# SCH_Clock_2021-09-15.net
KiCad netlist of a schematic drawn in EasyEDA
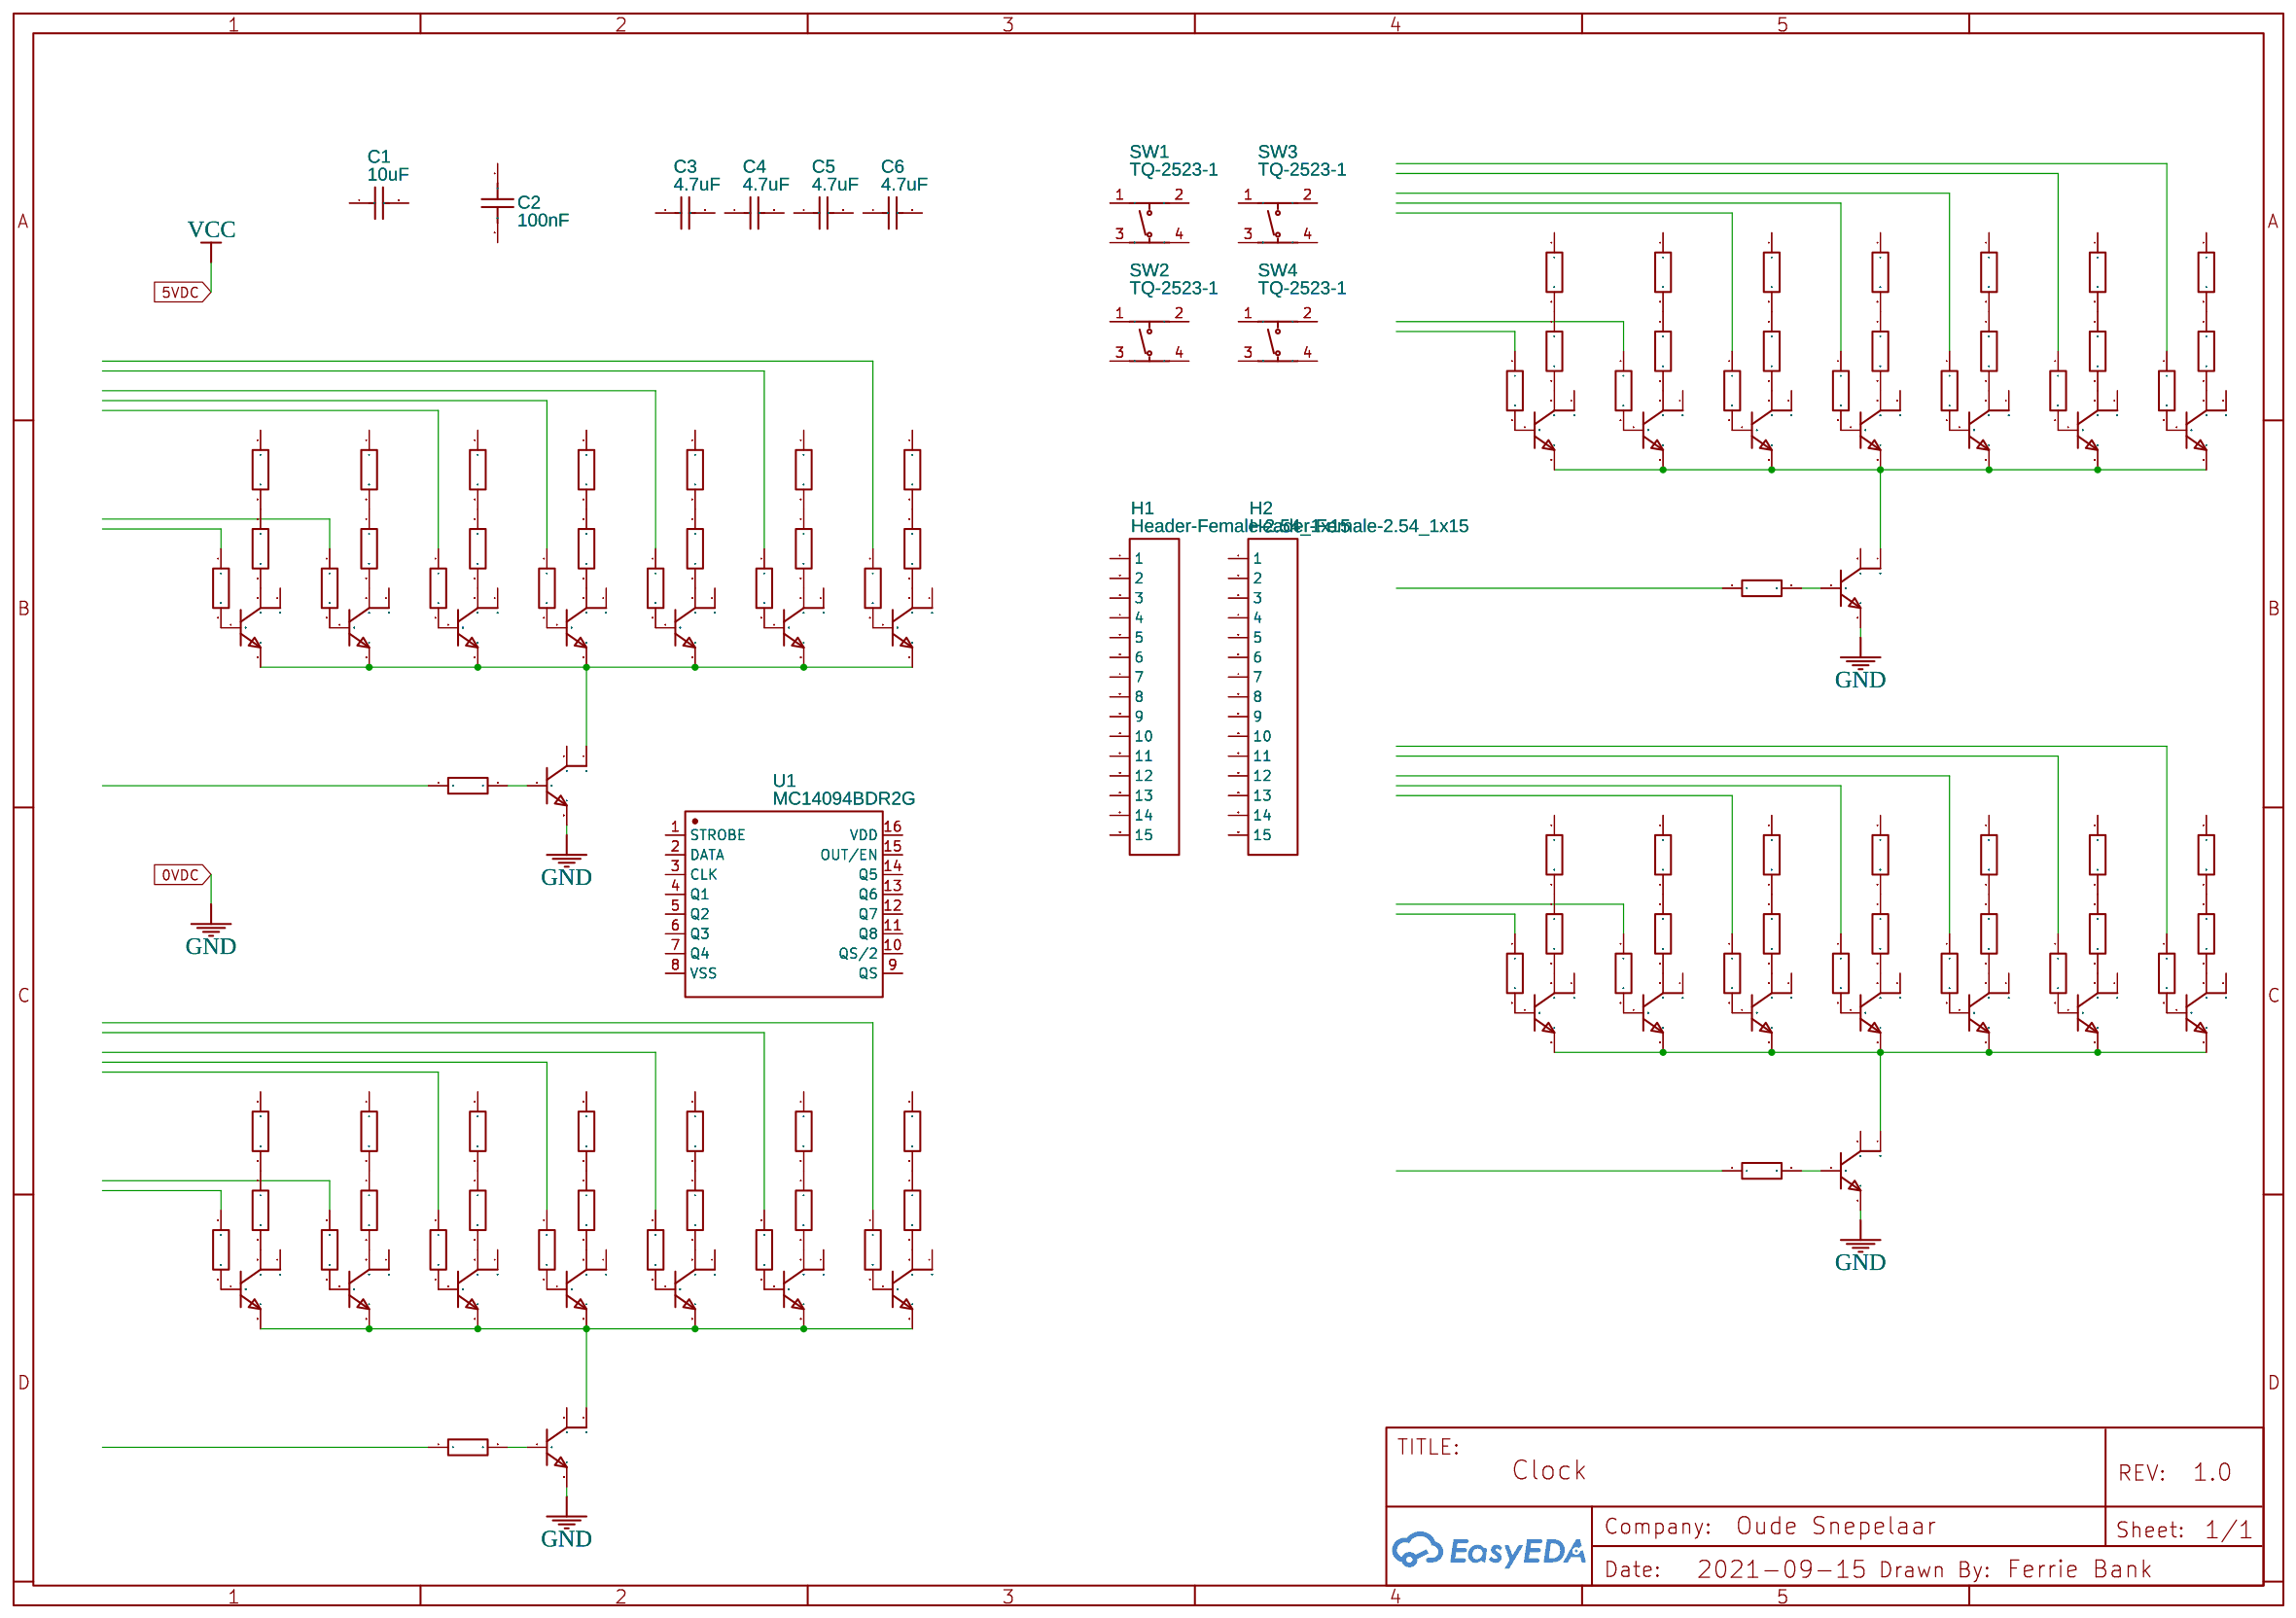
[diagram p0: schematic sheet]

(export (version "E")
  (design (tool "Eeschema 10.0.6"))
  (components
    (comp (ref "C1")
      (value "10uF")
      (fields
        (field (name "BOM_Manufacturer Part") "CL21A106KAYNNNE")
        (field (name "BOM_Supplier Part") "C15850")
      )
      (libsource (lib "") (part "CL21A106KAYNNNE"))
    )
    (comp (ref "C2")
      (value "100nF")
      (fields
        (field (name "BOM_Manufacturer Part") "CL10B104KB8WPNC")
        (field (name "BOM_Supplier Part") "C307348")
      )
      (libsource (lib "") (part "CL10B104KB8WPNC"))
    )
    (comp (ref "C3")
      (value "4.7uF")
      (fields
        (field (name "BOM_Manufacturer Part") "1206B475K500NT")
        (field (name "BOM_Supplier Part") "C29823")
      )
      (libsource (lib "") (part "1206B475K500NT"))
    )
    (comp (ref "C4")
      (value "4.7uF")
      (fields
        (field (name "BOM_Manufacturer Part") "1206B475K500NT")
        (field (name "BOM_Supplier Part") "C29823")
      )
      (libsource (lib "") (part "1206B475K500NT"))
    )
    (comp (ref "C5")
      (value "4.7uF")
      (fields
        (field (name "BOM_Manufacturer Part") "1206B475K500NT")
        (field (name "BOM_Supplier Part") "C29823")
      )
      (libsource (lib "") (part "1206B475K500NT"))
    )
    (comp (ref "C6")
      (value "4.7uF")
      (fields
        (field (name "BOM_Manufacturer Part") "1206B475K500NT")
        (field (name "BOM_Supplier Part") "C29823")
      )
      (libsource (lib "") (part "1206B475K500NT"))
    )
    (comp (ref "DGAQ1")
      (value "PZT2222A")
      (fields (field (name "BOM_Supplier Part") "C189428"))
      (libsource (lib "") (part "PZT2222A_1"))
    )
    (comp (ref "DGAQ2")
      (value "PZT2222A")
      (fields (field (name "BOM_Supplier Part") "C189428"))
      (libsource (lib "") (part "PZT2222A_1"))
    )
    (comp (ref "DGAQ3")
      (value "PZT2222A")
      (fields (field (name "BOM_Supplier Part") "C189428"))
      (libsource (lib "") (part "PZT2222A_1"))
    )
    (comp (ref "DGAQ4")
      (value "PZT2222A")
      (fields (field (name "BOM_Supplier Part") "C189428"))
      (libsource (lib "") (part "PZT2222A_1"))
    )
    (comp (ref "DGAQ5")
      (value "PZT2222A")
      (fields (field (name "BOM_Supplier Part") "C189428"))
      (libsource (lib "") (part "PZT2222A_1"))
    )
    (comp (ref "DGAQ6")
      (value "PZT2222A")
      (fields (field (name "BOM_Supplier Part") "C189428"))
      (libsource (lib "") (part "PZT2222A_1"))
    )
    (comp (ref "DGAQ7")
      (value "PZT2222A")
      (fields (field (name "BOM_Supplier Part") "C189428"))
      (libsource (lib "") (part "PZT2222A_1"))
    )
    (comp (ref "DGAQ8")
      (value "PZT2222A")
      (fields (field (name "BOM_Supplier Part") "C189428"))
      (libsource (lib "") (part "PZT2222A_1"))
    )
    (comp (ref "DGAR1")
      (value "75")
      (fields
        (field (name "BOM_Manufacturer Part") "0603WAF750JT5E")
        (field (name "BOM_Supplier Part") "C4275")
      )
      (libsource (lib "") (part "0603WAF750JT5E_2"))
    )
    (comp (ref "DGAR2")
      (value "75")
      (fields
        (field (name "BOM_Manufacturer Part") "0603WAF750JT5E")
        (field (name "BOM_Supplier Part") "C4275")
      )
      (libsource (lib "") (part "0603WAF750JT5E_2"))
    )
    (comp (ref "DGAR3")
      (value "75")
      (fields
        (field (name "BOM_Manufacturer Part") "0603WAF750JT5E")
        (field (name "BOM_Supplier Part") "C4275")
      )
      (libsource (lib "") (part "0603WAF750JT5E_2"))
    )
    (comp (ref "DGAR4")
      (value "75")
      (fields
        (field (name "BOM_Manufacturer Part") "0603WAF750JT5E")
        (field (name "BOM_Supplier Part") "C4275")
      )
      (libsource (lib "") (part "0603WAF750JT5E_2"))
    )
    (comp (ref "DGAR5")
      (value "75")
      (fields
        (field (name "BOM_Manufacturer Part") "0603WAF750JT5E")
        (field (name "BOM_Supplier Part") "C4275")
      )
      (libsource (lib "") (part "0603WAF750JT5E_2"))
    )
    (comp (ref "DGAR6")
      (value "75")
      (fields
        (field (name "BOM_Manufacturer Part") "0603WAF750JT5E")
        (field (name "BOM_Supplier Part") "C4275")
      )
      (libsource (lib "") (part "0603WAF750JT5E_2"))
    )
    (comp (ref "DGAR7")
      (value "75")
      (fields
        (field (name "BOM_Manufacturer Part") "0603WAF750JT5E")
        (field (name "BOM_Supplier Part") "C4275")
      )
      (libsource (lib "") (part "0603WAF750JT5E_2"))
    )
    (comp (ref "DGAR8")
      (value "75")
      (fields
        (field (name "BOM_Manufacturer Part") "0603WAF750JT5E")
        (field (name "BOM_Supplier Part") "C4275")
      )
      (libsource (lib "") (part "0603WAF750JT5E_2"))
    )
    (comp (ref "DGAR9")
      (value "75")
      (fields
        (field (name "BOM_Manufacturer Part") "0603WAF750JT5E")
        (field (name "BOM_Supplier Part") "C4275")
      )
      (libsource (lib "") (part "0603WAF750JT5E_2"))
    )
    (comp (ref "DGAR10")
      (value "75")
      (fields
        (field (name "BOM_Manufacturer Part") "0603WAF750JT5E")
        (field (name "BOM_Supplier Part") "C4275")
      )
      (libsource (lib "") (part "0603WAF750JT5E_2"))
    )
    (comp (ref "DGAR11")
      (value "75")
      (fields
        (field (name "BOM_Manufacturer Part") "0603WAF750JT5E")
        (field (name "BOM_Supplier Part") "C4275")
      )
      (libsource (lib "") (part "0603WAF750JT5E_2"))
    )
    (comp (ref "DGAR12")
      (value "75")
      (fields
        (field (name "BOM_Manufacturer Part") "0603WAF750JT5E")
        (field (name "BOM_Supplier Part") "C4275")
      )
      (libsource (lib "") (part "0603WAF750JT5E_2"))
    )
    (comp (ref "DGAR13")
      (value "75")
      (fields
        (field (name "BOM_Manufacturer Part") "0603WAF750JT5E")
        (field (name "BOM_Supplier Part") "C4275")
      )
      (libsource (lib "") (part "0603WAF750JT5E_2"))
    )
    (comp (ref "DGAR14")
      (value "75")
      (fields
        (field (name "BOM_Manufacturer Part") "0603WAF750JT5E")
        (field (name "BOM_Supplier Part") "C4275")
      )
      (libsource (lib "") (part "0603WAF750JT5E_2"))
    )
    (comp (ref "DGAR15")
      (value "33")
      (fields
        (field (name "BOM_Manufacturer Part") "0603WAF330JT5E")
        (field (name "BOM_Supplier Part") "C23140")
      )
      (libsource (lib "") (part "0603WAF330JT5E_6"))
    )
    (comp (ref "DGAR16")
      (value "33")
      (fields
        (field (name "BOM_Manufacturer Part") "0603WAF330JT5E")
        (field (name "BOM_Supplier Part") "C23140")
      )
      (libsource (lib "") (part "0603WAF330JT5E_1"))
    )
    (comp (ref "DGAR17")
      (value "33")
      (fields
        (field (name "BOM_Manufacturer Part") "0603WAF330JT5E")
        (field (name "BOM_Supplier Part") "C23140")
      )
      (libsource (lib "") (part "0603WAF330JT5E_1"))
    )
    (comp (ref "DGAR18")
      (value "33")
      (fields
        (field (name "BOM_Manufacturer Part") "0603WAF330JT5E")
        (field (name "BOM_Supplier Part") "C23140")
      )
      (libsource (lib "") (part "0603WAF330JT5E_1"))
    )
    (comp (ref "DGAR19")
      (value "33")
      (fields
        (field (name "BOM_Manufacturer Part") "0603WAF330JT5E")
        (field (name "BOM_Supplier Part") "C23140")
      )
      (libsource (lib "") (part "0603WAF330JT5E_1"))
    )
    (comp (ref "DGAR20")
      (value "33")
      (fields
        (field (name "BOM_Manufacturer Part") "0603WAF330JT5E")
        (field (name "BOM_Supplier Part") "C23140")
      )
      (libsource (lib "") (part "0603WAF330JT5E_1"))
    )
    (comp (ref "DGAR21")
      (value "33")
      (fields
        (field (name "BOM_Manufacturer Part") "0603WAF330JT5E")
        (field (name "BOM_Supplier Part") "C23140")
      )
      (libsource (lib "") (part "0603WAF330JT5E_1"))
    )
    (comp (ref "DGAR22")
      (value "33")
      (fields
        (field (name "BOM_Manufacturer Part") "0603WAF330JT5E")
        (field (name "BOM_Supplier Part") "C23140")
      )
      (libsource (lib "") (part "0603WAF330JT5E_1"))
    )
    (comp (ref "DGBQ1")
      (value "PZT2222A")
      (fields (field (name "BOM_Supplier Part") "C189428"))
      (libsource (lib "") (part "PZT2222A"))
    )
    (comp (ref "DGBQ2")
      (value "PZT2222A")
      (fields (field (name "BOM_Supplier Part") "C189428"))
      (libsource (lib "") (part "PZT2222A"))
    )
    (comp (ref "DGBQ3")
      (value "PZT2222A")
      (fields (field (name "BOM_Supplier Part") "C189428"))
      (libsource (lib "") (part "PZT2222A"))
    )
    (comp (ref "DGBQ4")
      (value "PZT2222A")
      (fields (field (name "BOM_Supplier Part") "C189428"))
      (libsource (lib "") (part "PZT2222A"))
    )
    (comp (ref "DGBQ5")
      (value "PZT2222A")
      (fields (field (name "BOM_Supplier Part") "C189428"))
      (libsource (lib "") (part "PZT2222A"))
    )
    (comp (ref "DGBQ6")
      (value "PZT2222A")
      (fields (field (name "BOM_Supplier Part") "C189428"))
      (libsource (lib "") (part "PZT2222A"))
    )
    (comp (ref "DGBQ7")
      (value "PZT2222A")
      (fields (field (name "BOM_Supplier Part") "C189428"))
      (libsource (lib "") (part "PZT2222A"))
    )
    (comp (ref "DGBQ8")
      (value "PZT2222A")
      (fields (field (name "BOM_Supplier Part") "C189428"))
      (libsource (lib "") (part "PZT2222A"))
    )
    (comp (ref "DGBR1")
      (value "75")
      (fields
        (field (name "BOM_Manufacturer Part") "0603WAF750JT5E")
        (field (name "BOM_Supplier Part") "C4275")
      )
      (libsource (lib "") (part "0603WAF750JT5E_3"))
    )
    (comp (ref "DGBR2")
      (value "75")
      (fields
        (field (name "BOM_Manufacturer Part") "0603WAF750JT5E")
        (field (name "BOM_Supplier Part") "C4275")
      )
      (libsource (lib "") (part "0603WAF750JT5E_3"))
    )
    (comp (ref "DGBR3")
      (value "75")
      (fields
        (field (name "BOM_Manufacturer Part") "0603WAF750JT5E")
        (field (name "BOM_Supplier Part") "C4275")
      )
      (libsource (lib "") (part "0603WAF750JT5E_3"))
    )
    (comp (ref "DGBR4")
      (value "75")
      (fields
        (field (name "BOM_Manufacturer Part") "0603WAF750JT5E")
        (field (name "BOM_Supplier Part") "C4275")
      )
      (libsource (lib "") (part "0603WAF750JT5E_3"))
    )
    (comp (ref "DGBR5")
      (value "75")
      (fields
        (field (name "BOM_Manufacturer Part") "0603WAF750JT5E")
        (field (name "BOM_Supplier Part") "C4275")
      )
      (libsource (lib "") (part "0603WAF750JT5E_3"))
    )
    (comp (ref "DGBR6")
      (value "75")
      (fields
        (field (name "BOM_Manufacturer Part") "0603WAF750JT5E")
        (field (name "BOM_Supplier Part") "C4275")
      )
      (libsource (lib "") (part "0603WAF750JT5E_3"))
    )
    (comp (ref "DGBR7")
      (value "75")
      (fields
        (field (name "BOM_Manufacturer Part") "0603WAF750JT5E")
        (field (name "BOM_Supplier Part") "C4275")
      )
      (libsource (lib "") (part "0603WAF750JT5E_3"))
    )
    (comp (ref "DGBR8")
      (value "75")
      (fields
        (field (name "BOM_Manufacturer Part") "0603WAF750JT5E")
        (field (name "BOM_Supplier Part") "C4275")
      )
      (libsource (lib "") (part "0603WAF750JT5E_3"))
    )
    (comp (ref "DGBR9")
      (value "75")
      (fields
        (field (name "BOM_Manufacturer Part") "0603WAF750JT5E")
        (field (name "BOM_Supplier Part") "C4275")
      )
      (libsource (lib "") (part "0603WAF750JT5E_3"))
    )
    (comp (ref "DGBR10")
      (value "75")
      (fields
        (field (name "BOM_Manufacturer Part") "0603WAF750JT5E")
        (field (name "BOM_Supplier Part") "C4275")
      )
      (libsource (lib "") (part "0603WAF750JT5E_3"))
    )
    (comp (ref "DGBR11")
      (value "75")
      (fields
        (field (name "BOM_Manufacturer Part") "0603WAF750JT5E")
        (field (name "BOM_Supplier Part") "C4275")
      )
      (libsource (lib "") (part "0603WAF750JT5E_3"))
    )
    (comp (ref "DGBR12")
      (value "75")
      (fields
        (field (name "BOM_Manufacturer Part") "0603WAF750JT5E")
        (field (name "BOM_Supplier Part") "C4275")
      )
      (libsource (lib "") (part "0603WAF750JT5E_3"))
    )
    (comp (ref "DGBR13")
      (value "75")
      (fields
        (field (name "BOM_Manufacturer Part") "0603WAF750JT5E")
        (field (name "BOM_Supplier Part") "C4275")
      )
      (libsource (lib "") (part "0603WAF750JT5E_3"))
    )
    (comp (ref "DGBR14")
      (value "75")
      (fields
        (field (name "BOM_Manufacturer Part") "0603WAF750JT5E")
        (field (name "BOM_Supplier Part") "C4275")
      )
      (libsource (lib "") (part "0603WAF750JT5E_3"))
    )
    (comp (ref "DGBR15")
      (value "33")
      (fields
        (field (name "BOM_Manufacturer Part") "0603WAF330JT5E")
        (field (name "BOM_Supplier Part") "C23140")
      )
      (libsource (lib "") (part "0603WAF330JT5E_5"))
    )
    (comp (ref "DGBR16")
      (value "33")
      (fields
        (field (name "BOM_Manufacturer Part") "0603WAF330JT5E")
        (field (name "BOM_Supplier Part") "C23140")
      )
      (libsource (lib "") (part "0603WAF330JT5E_3"))
    )
    (comp (ref "DGBR17")
      (value "33")
      (fields
        (field (name "BOM_Manufacturer Part") "0603WAF330JT5E")
        (field (name "BOM_Supplier Part") "C23140")
      )
      (libsource (lib "") (part "0603WAF330JT5E_3"))
    )
    (comp (ref "DGBR18")
      (value "33")
      (fields
        (field (name "BOM_Manufacturer Part") "0603WAF330JT5E")
        (field (name "BOM_Supplier Part") "C23140")
      )
      (libsource (lib "") (part "0603WAF330JT5E_3"))
    )
    (comp (ref "DGBR19")
      (value "33")
      (fields
        (field (name "BOM_Manufacturer Part") "0603WAF330JT5E")
        (field (name "BOM_Supplier Part") "C23140")
      )
      (libsource (lib "") (part "0603WAF330JT5E_3"))
    )
    (comp (ref "DGBR20")
      (value "33")
      (fields
        (field (name "BOM_Manufacturer Part") "0603WAF330JT5E")
        (field (name "BOM_Supplier Part") "C23140")
      )
      (libsource (lib "") (part "0603WAF330JT5E_3"))
    )
    (comp (ref "DGBR21")
      (value "33")
      (fields
        (field (name "BOM_Manufacturer Part") "0603WAF330JT5E")
        (field (name "BOM_Supplier Part") "C23140")
      )
      (libsource (lib "") (part "0603WAF330JT5E_3"))
    )
    (comp (ref "DGBR22")
      (value "33")
      (fields
        (field (name "BOM_Manufacturer Part") "0603WAF330JT5E")
        (field (name "BOM_Supplier Part") "C23140")
      )
      (libsource (lib "") (part "0603WAF330JT5E_3"))
    )
    (comp (ref "DGCQ1")
      (value "PZT2222A")
      (fields (field (name "BOM_Supplier Part") "C189428"))
      (libsource (lib "") (part "PZT2222A_3"))
    )
    (comp (ref "DGCQ2")
      (value "PZT2222A")
      (fields (field (name "BOM_Supplier Part") "C189428"))
      (libsource (lib "") (part "PZT2222A_3"))
    )
    (comp (ref "DGCQ3")
      (value "PZT2222A")
      (fields (field (name "BOM_Supplier Part") "C189428"))
      (libsource (lib "") (part "PZT2222A_3"))
    )
    (comp (ref "DGCQ4")
      (value "PZT2222A")
      (fields (field (name "BOM_Supplier Part") "C189428"))
      (libsource (lib "") (part "PZT2222A_3"))
    )
    (comp (ref "DGCQ5")
      (value "PZT2222A")
      (fields (field (name "BOM_Supplier Part") "C189428"))
      (libsource (lib "") (part "PZT2222A_3"))
    )
    (comp (ref "DGCQ6")
      (value "PZT2222A")
      (fields (field (name "BOM_Supplier Part") "C189428"))
      (libsource (lib "") (part "PZT2222A_3"))
    )
    (comp (ref "DGCQ7")
      (value "PZT2222A")
      (fields (field (name "BOM_Supplier Part") "C189428"))
      (libsource (lib "") (part "PZT2222A_3"))
    )
    (comp (ref "DGCQ8")
      (value "PZT2222A")
      (fields (field (name "BOM_Supplier Part") "C189428"))
      (libsource (lib "") (part "PZT2222A_3"))
    )
    (comp (ref "DGCR1")
      (value "75")
      (fields
        (field (name "BOM_Manufacturer Part") "0603WAF750JT5E")
        (field (name "BOM_Supplier Part") "C4275")
      )
      (libsource (lib "") (part "0603WAF750JT5E"))
    )
    (comp (ref "DGCR2")
      (value "75")
      (fields
        (field (name "BOM_Manufacturer Part") "0603WAF750JT5E")
        (field (name "BOM_Supplier Part") "C4275")
      )
      (libsource (lib "") (part "0603WAF750JT5E"))
    )
    (comp (ref "DGCR3")
      (value "75")
      (fields
        (field (name "BOM_Manufacturer Part") "0603WAF750JT5E")
        (field (name "BOM_Supplier Part") "C4275")
      )
      (libsource (lib "") (part "0603WAF750JT5E"))
    )
    (comp (ref "DGCR4")
      (value "75")
      (fields
        (field (name "BOM_Manufacturer Part") "0603WAF750JT5E")
        (field (name "BOM_Supplier Part") "C4275")
      )
      (libsource (lib "") (part "0603WAF750JT5E"))
    )
    (comp (ref "DGCR5")
      (value "75")
      (fields
        (field (name "BOM_Manufacturer Part") "0603WAF750JT5E")
        (field (name "BOM_Supplier Part") "C4275")
      )
      (libsource (lib "") (part "0603WAF750JT5E"))
    )
    (comp (ref "DGCR6")
      (value "75")
      (fields
        (field (name "BOM_Manufacturer Part") "0603WAF750JT5E")
        (field (name "BOM_Supplier Part") "C4275")
      )
      (libsource (lib "") (part "0603WAF750JT5E"))
    )
    (comp (ref "DGCR7")
      (value "75")
      (fields
        (field (name "BOM_Manufacturer Part") "0603WAF750JT5E")
        (field (name "BOM_Supplier Part") "C4275")
      )
      (libsource (lib "") (part "0603WAF750JT5E"))
    )
    (comp (ref "DGCR8")
      (value "75")
      (fields
        (field (name "BOM_Manufacturer Part") "0603WAF750JT5E")
        (field (name "BOM_Supplier Part") "C4275")
      )
      (libsource (lib "") (part "0603WAF750JT5E"))
    )
    (comp (ref "DGCR9")
      (value "75")
      (fields
        (field (name "BOM_Manufacturer Part") "0603WAF750JT5E")
        (field (name "BOM_Supplier Part") "C4275")
      )
      (libsource (lib "") (part "0603WAF750JT5E"))
    )
    (comp (ref "DGCR10")
      (value "75")
      (fields
        (field (name "BOM_Manufacturer Part") "0603WAF750JT5E")
        (field (name "BOM_Supplier Part") "C4275")
      )
      (libsource (lib "") (part "0603WAF750JT5E"))
    )
    (comp (ref "DGCR11")
      (value "75")
      (fields
        (field (name "BOM_Manufacturer Part") "0603WAF750JT5E")
        (field (name "BOM_Supplier Part") "C4275")
      )
      (libsource (lib "") (part "0603WAF750JT5E"))
    )
    (comp (ref "DGCR12")
      (value "75")
      (fields
        (field (name "BOM_Manufacturer Part") "0603WAF750JT5E")
        (field (name "BOM_Supplier Part") "C4275")
      )
      (libsource (lib "") (part "0603WAF750JT5E"))
    )
    (comp (ref "DGCR13")
      (value "75")
      (fields
        (field (name "BOM_Manufacturer Part") "0603WAF750JT5E")
        (field (name "BOM_Supplier Part") "C4275")
      )
      (libsource (lib "") (part "0603WAF750JT5E"))
    )
    (comp (ref "DGCR14")
      (value "75")
      (fields
        (field (name "BOM_Manufacturer Part") "0603WAF750JT5E")
        (field (name "BOM_Supplier Part") "C4275")
      )
      (libsource (lib "") (part "0603WAF750JT5E"))
    )
    (comp (ref "DGCR15")
      (value "33")
      (fields
        (field (name "BOM_Manufacturer Part") "0603WAF330JT5E")
        (field (name "BOM_Supplier Part") "C23140")
      )
      (libsource (lib "") (part "0603WAF330JT5E_4"))
    )
    (comp (ref "DGCR16")
      (value "33")
      (fields
        (field (name "BOM_Manufacturer Part") "0603WAF330JT5E")
        (field (name "BOM_Supplier Part") "C23140")
      )
      (libsource (lib "") (part "0603WAF330JT5E_2"))
    )
    (comp (ref "DGCR17")
      (value "33")
      (fields
        (field (name "BOM_Manufacturer Part") "0603WAF330JT5E")
        (field (name "BOM_Supplier Part") "C23140")
      )
      (libsource (lib "") (part "0603WAF330JT5E_2"))
    )
    (comp (ref "DGCR18")
      (value "33")
      (fields
        (field (name "BOM_Manufacturer Part") "0603WAF330JT5E")
        (field (name "BOM_Supplier Part") "C23140")
      )
      (libsource (lib "") (part "0603WAF330JT5E_2"))
    )
    (comp (ref "DGCR19")
      (value "33")
      (fields
        (field (name "BOM_Manufacturer Part") "0603WAF330JT5E")
        (field (name "BOM_Supplier Part") "C23140")
      )
      (libsource (lib "") (part "0603WAF330JT5E_2"))
    )
    (comp (ref "DGCR20")
      (value "33")
      (fields
        (field (name "BOM_Manufacturer Part") "0603WAF330JT5E")
        (field (name "BOM_Supplier Part") "C23140")
      )
      (libsource (lib "") (part "0603WAF330JT5E_2"))
    )
    (comp (ref "DGCR21")
      (value "33")
      (fields
        (field (name "BOM_Manufacturer Part") "0603WAF330JT5E")
        (field (name "BOM_Supplier Part") "C23140")
      )
      (libsource (lib "") (part "0603WAF330JT5E_2"))
    )
    (comp (ref "DGCR22")
      (value "33")
      (fields
        (field (name "BOM_Manufacturer Part") "0603WAF330JT5E")
        (field (name "BOM_Supplier Part") "C23140")
      )
      (libsource (lib "") (part "0603WAF330JT5E_2"))
    )
    (comp (ref "DGDQ1")
      (value "PZT2222A")
      (fields (field (name "BOM_Supplier Part") "C189428"))
      (libsource (lib "") (part "PZT2222A_2"))
    )
    (comp (ref "DGDQ2")
      (value "PZT2222A")
      (fields (field (name "BOM_Supplier Part") "C189428"))
      (libsource (lib "") (part "PZT2222A_2"))
    )
    (comp (ref "DGDQ3")
      (value "PZT2222A")
      (fields (field (name "BOM_Supplier Part") "C189428"))
      (libsource (lib "") (part "PZT2222A_2"))
    )
    (comp (ref "DGDQ4")
      (value "PZT2222A")
      (fields (field (name "BOM_Supplier Part") "C189428"))
      (libsource (lib "") (part "PZT2222A_2"))
    )
    (comp (ref "DGDQ5")
      (value "PZT2222A")
      (fields (field (name "BOM_Supplier Part") "C189428"))
      (libsource (lib "") (part "PZT2222A_2"))
    )
    (comp (ref "DGDQ6")
      (value "PZT2222A")
      (fields (field (name "BOM_Supplier Part") "C189428"))
      (libsource (lib "") (part "PZT2222A_2"))
    )
    (comp (ref "DGDQ7")
      (value "PZT2222A")
      (fields (field (name "BOM_Supplier Part") "C189428"))
      (libsource (lib "") (part "PZT2222A_2"))
    )
    (comp (ref "DGDQ8")
      (value "PZT2222A")
      (fields (field (name "BOM_Supplier Part") "C189428"))
      (libsource (lib "") (part "PZT2222A_2"))
    )
    (comp (ref "DGDR1")
      (value "75")
      (fields
        (field (name "BOM_Manufacturer Part") "0603WAF750JT5E")
        (field (name "BOM_Supplier Part") "C4275")
      )
      (libsource (lib "") (part "0603WAF750JT5E_1"))
    )
    (comp (ref "DGDR2")
      (value "75")
      (fields
        (field (name "BOM_Manufacturer Part") "0603WAF750JT5E")
        (field (name "BOM_Supplier Part") "C4275")
      )
      (libsource (lib "") (part "0603WAF750JT5E_1"))
    )
    (comp (ref "DGDR3")
      (value "75")
      (fields
        (field (name "BOM_Manufacturer Part") "0603WAF750JT5E")
        (field (name "BOM_Supplier Part") "C4275")
      )
      (libsource (lib "") (part "0603WAF750JT5E_1"))
    )
    (comp (ref "DGDR4")
      (value "75")
      (fields
        (field (name "BOM_Manufacturer Part") "0603WAF750JT5E")
        (field (name "BOM_Supplier Part") "C4275")
      )
      (libsource (lib "") (part "0603WAF750JT5E_1"))
    )
    (comp (ref "DGDR5")
      (value "75")
      (fields
        (field (name "BOM_Manufacturer Part") "0603WAF750JT5E")
        (field (name "BOM_Supplier Part") "C4275")
      )
      (libsource (lib "") (part "0603WAF750JT5E_1"))
    )
    (comp (ref "DGDR6")
      (value "75")
      (fields
        (field (name "BOM_Manufacturer Part") "0603WAF750JT5E")
        (field (name "BOM_Supplier Part") "C4275")
      )
      (libsource (lib "") (part "0603WAF750JT5E_1"))
    )
    (comp (ref "DGDR7")
      (value "75")
      (fields
        (field (name "BOM_Manufacturer Part") "0603WAF750JT5E")
        (field (name "BOM_Supplier Part") "C4275")
      )
      (libsource (lib "") (part "0603WAF750JT5E_1"))
    )
    (comp (ref "DGDR8")
      (value "75")
      (fields
        (field (name "BOM_Manufacturer Part") "0603WAF750JT5E")
        (field (name "BOM_Supplier Part") "C4275")
      )
      (libsource (lib "") (part "0603WAF750JT5E_1"))
    )
    (comp (ref "DGDR9")
      (value "75")
      (fields
        (field (name "BOM_Manufacturer Part") "0603WAF750JT5E")
        (field (name "BOM_Supplier Part") "C4275")
      )
      (libsource (lib "") (part "0603WAF750JT5E_1"))
    )
    (comp (ref "DGDR10")
      (value "75")
      (fields
        (field (name "BOM_Manufacturer Part") "0603WAF750JT5E")
        (field (name "BOM_Supplier Part") "C4275")
      )
      (libsource (lib "") (part "0603WAF750JT5E_1"))
    )
    (comp (ref "DGDR11")
      (value "75")
      (fields
        (field (name "BOM_Manufacturer Part") "0603WAF750JT5E")
        (field (name "BOM_Supplier Part") "C4275")
      )
      (libsource (lib "") (part "0603WAF750JT5E_1"))
    )
    (comp (ref "DGDR12")
      (value "75")
      (fields
        (field (name "BOM_Manufacturer Part") "0603WAF750JT5E")
        (field (name "BOM_Supplier Part") "C4275")
      )
      (libsource (lib "") (part "0603WAF750JT5E_1"))
    )
    (comp (ref "DGDR13")
      (value "75")
      (fields
        (field (name "BOM_Manufacturer Part") "0603WAF750JT5E")
        (field (name "BOM_Supplier Part") "C4275")
      )
      (libsource (lib "") (part "0603WAF750JT5E_1"))
    )
    (comp (ref "DGDR14")
      (value "75")
      (fields
        (field (name "BOM_Manufacturer Part") "0603WAF750JT5E")
        (field (name "BOM_Supplier Part") "C4275")
      )
      (libsource (lib "") (part "0603WAF750JT5E_1"))
    )
    (comp (ref "DGDR15")
      (value "33")
      (fields
        (field (name "BOM_Manufacturer Part") "0603WAF330JT5E")
        (field (name "BOM_Supplier Part") "C23140")
      )
      (libsource (lib "") (part "0603WAF330JT5E_7"))
    )
    (comp (ref "DGDR16")
      (value "33")
      (fields
        (field (name "BOM_Manufacturer Part") "0603WAF330JT5E")
        (field (name "BOM_Supplier Part") "C23140")
      )
      (libsource (lib "") (part "0603WAF330JT5E"))
    )
    (comp (ref "DGDR17")
      (value "33")
      (fields
        (field (name "BOM_Manufacturer Part") "0603WAF330JT5E")
        (field (name "BOM_Supplier Part") "C23140")
      )
      (libsource (lib "") (part "0603WAF330JT5E"))
    )
    (comp (ref "DGDR18")
      (value "33")
      (fields
        (field (name "BOM_Manufacturer Part") "0603WAF330JT5E")
        (field (name "BOM_Supplier Part") "C23140")
      )
      (libsource (lib "") (part "0603WAF330JT5E"))
    )
    (comp (ref "DGDR19")
      (value "33")
      (fields
        (field (name "BOM_Manufacturer Part") "0603WAF330JT5E")
        (field (name "BOM_Supplier Part") "C23140")
      )
      (libsource (lib "") (part "0603WAF330JT5E"))
    )
    (comp (ref "DGDR20")
      (value "33")
      (fields
        (field (name "BOM_Manufacturer Part") "0603WAF330JT5E")
        (field (name "BOM_Supplier Part") "C23140")
      )
      (libsource (lib "") (part "0603WAF330JT5E"))
    )
    (comp (ref "DGDR21")
      (value "33")
      (fields
        (field (name "BOM_Manufacturer Part") "0603WAF330JT5E")
        (field (name "BOM_Supplier Part") "C23140")
      )
      (libsource (lib "") (part "0603WAF330JT5E"))
    )
    (comp (ref "DGDR22")
      (value "33")
      (fields
        (field (name "BOM_Manufacturer Part") "0603WAF330JT5E")
        (field (name "BOM_Supplier Part") "C23140")
      )
      (libsource (lib "") (part "0603WAF330JT5E"))
    )
    (comp (ref "H1")
      (value "Header-Female-2.54_1x15")
      (fields
        (field (name "BOM_Manufacturer Part") "220S-1*15P H=8.5MM Ytype Gold-plated")
        (field (name "BOM_Supplier Part") "C124408")
      )
      (libsource (lib "") (part "Header-Female-2.54_1x15"))
    )
    (comp (ref "H2")
      (value "Header-Female-2.54_1x15")
      (fields
        (field (name "BOM_Manufacturer Part") "220S-1*15P H=8.5MM Ytype Gold-plated")
        (field (name "BOM_Supplier Part") "C124408")
      )
      (libsource (lib "") (part "Header-Female-2.54_1x15"))
    )
    (comp (ref "SW1")
      (value "TQ-2523-1")
      (fields (field (name "BOM_Supplier Part") "C669810"))
      (libsource (lib "") (part "TQ-2523-1"))
    )
    (comp (ref "SW2")
      (value "TQ-2523-1")
      (fields (field (name "BOM_Supplier Part") "C669810"))
      (libsource (lib "") (part "TQ-2523-1"))
    )
    (comp (ref "SW3")
      (value "TQ-2523-1")
      (fields (field (name "BOM_Supplier Part") "C669810"))
      (libsource (lib "") (part "TQ-2523-1"))
    )
    (comp (ref "SW4")
      (value "TQ-2523-1")
      (fields (field (name "BOM_Supplier Part") "C669810"))
      (libsource (lib "") (part "TQ-2523-1"))
    )
    (comp (ref "U1")
      (value "MC14094BDR2G")
      (fields (field (name "BOM_Supplier Part") "C161627"))
      (libsource (lib "") (part "MC14094BDR2G"))
    )
  )
  (nets
    (net (code "1") (name "0VDC") (class "Default")
      (node (ref "DGAQ2") (pin "3") (pinfunction "E_3") (pintype "unspecified"))
      (node (ref "DGBQ2") (pin "3") (pinfunction "E_3") (pintype "unspecified"))
      (node (ref "DGCQ2") (pin "3") (pinfunction "E_3") (pintype "unspecified"))
      (node (ref "DGDQ2") (pin "3") (pinfunction "E_3") (pintype "unspecified"))
    )
    (net (code "3") (name "Net-(DGAQ1-B)") (class "Default")
      (node (ref "DGAQ1") (pin "1") (pinfunction "B_1") (pintype "unspecified"))
      (node (ref "DGAR16") (pin "2") (pinfunction "2_2") (pintype "input"))
    )
    (net (code "4") (name "Net-(DGAQ1-C-Pad2)") (class "Default")
      (node (ref "DGAQ1") (pin "2") (pinfunction "C_2") (pintype "unspecified"))
      (node (ref "DGAR3") (pin "2") (pinfunction "2_2") (pintype "input"))
    )
    (net (code "5") (name "Net-(DGAQ1-E)") (class "Default")
      (node (ref "DGAQ1") (pin "3") (pinfunction "E_3") (pintype "unspecified"))
      (node (ref "DGAQ2") (pin "4") (pinfunction "C_4") (pintype "unspecified"))
      (node (ref "DGAQ3") (pin "3") (pinfunction "E_3") (pintype "unspecified"))
      (node (ref "DGAQ4") (pin "3") (pinfunction "E_3") (pintype "unspecified"))
      (node (ref "DGAQ5") (pin "3") (pinfunction "E_3") (pintype "unspecified"))
      (node (ref "DGAQ6") (pin "3") (pinfunction "E_3") (pintype "unspecified"))
      (node (ref "DGAQ7") (pin "3") (pinfunction "E_3") (pintype "unspecified"))
      (node (ref "DGAQ8") (pin "3") (pinfunction "E_3") (pintype "unspecified"))
    )
    (net (code "6") (name "Net-(DGAQ2-B)") (class "Default")
      (node (ref "DGAQ2") (pin "1") (pinfunction "B_1") (pintype "unspecified"))
      (node (ref "DGAR15") (pin "2") (pinfunction "2_2") (pintype "input"))
    )
    (net (code "7") (name "Net-(DGAQ3-B)") (class "Default")
      (node (ref "DGAQ3") (pin "1") (pinfunction "B_1") (pintype "unspecified"))
      (node (ref "DGAR22") (pin "2") (pinfunction "2_2") (pintype "input"))
    )
    (net (code "8") (name "Net-(DGAQ3-C-Pad2)") (class "Default")
      (node (ref "DGAQ3") (pin "2") (pinfunction "C_2") (pintype "unspecified"))
      (node (ref "DGAR14") (pin "2") (pinfunction "2_2") (pintype "input"))
    )
    (net (code "9") (name "Net-(DGAQ4-B)") (class "Default")
      (node (ref "DGAQ4") (pin "1") (pinfunction "B_1") (pintype "unspecified"))
      (node (ref "DGAR17") (pin "2") (pinfunction "2_2") (pintype "input"))
    )
    (net (code "10") (name "Net-(DGAQ4-C-Pad2)") (class "Default")
      (node (ref "DGAQ4") (pin "2") (pinfunction "C_2") (pintype "unspecified"))
      (node (ref "DGAR4") (pin "2") (pinfunction "2_2") (pintype "input"))
    )
    (net (code "11") (name "Net-(DGAQ5-B)") (class "Default")
      (node (ref "DGAQ5") (pin "1") (pinfunction "B_1") (pintype "unspecified"))
      (node (ref "DGAR19") (pin "2") (pinfunction "2_2") (pintype "input"))
    )
    (net (code "12") (name "Net-(DGAQ5-C-Pad2)") (class "Default")
      (node (ref "DGAQ5") (pin "2") (pinfunction "C_2") (pintype "unspecified"))
      (node (ref "DGAR8") (pin "2") (pinfunction "2_2") (pintype "input"))
    )
    (net (code "13") (name "Net-(DGAQ6-B)") (class "Default")
      (node (ref "DGAQ6") (pin "1") (pinfunction "B_1") (pintype "unspecified"))
      (node (ref "DGAR18") (pin "2") (pinfunction "2_2") (pintype "input"))
    )
    (net (code "14") (name "Net-(DGAQ6-C-Pad2)") (class "Default")
      (node (ref "DGAQ6") (pin "2") (pinfunction "C_2") (pintype "unspecified"))
      (node (ref "DGAR6") (pin "2") (pinfunction "2_2") (pintype "input"))
    )
    (net (code "15") (name "Net-(DGAQ7-B)") (class "Default")
      (node (ref "DGAQ7") (pin "1") (pinfunction "B_1") (pintype "unspecified"))
      (node (ref "DGAR21") (pin "2") (pinfunction "2_2") (pintype "input"))
    )
    (net (code "16") (name "Net-(DGAQ7-C-Pad2)") (class "Default")
      (node (ref "DGAQ7") (pin "2") (pinfunction "C_2") (pintype "unspecified"))
      (node (ref "DGAR12") (pin "2") (pinfunction "2_2") (pintype "input"))
    )
    (net (code "17") (name "Net-(DGAQ8-B)") (class "Default")
      (node (ref "DGAQ8") (pin "1") (pinfunction "B_1") (pintype "unspecified"))
      (node (ref "DGAR20") (pin "2") (pinfunction "2_2") (pintype "input"))
    )
    (net (code "18") (name "Net-(DGAQ8-C-Pad2)") (class "Default")
      (node (ref "DGAQ8") (pin "2") (pinfunction "C_2") (pintype "unspecified"))
      (node (ref "DGAR10") (pin "2") (pinfunction "2_2") (pintype "input"))
    )
    (net (code "19") (name "Net-(DGAR1-Pad2)") (class "Default")
      (node (ref "DGAR1") (pin "2") (pinfunction "2_2") (pintype "input"))
      (node (ref "DGAR3") (pin "1") (pinfunction "1_1") (pintype "input"))
    )
    (net (code "20") (name "Net-(DGAR2-Pad2)") (class "Default")
      (node (ref "DGAR2") (pin "2") (pinfunction "2_2") (pintype "input"))
      (node (ref "DGAR4") (pin "1") (pinfunction "1_1") (pintype "input"))
    )
    (net (code "21") (name "Net-(DGAR5-Pad2)") (class "Default")
      (node (ref "DGAR5") (pin "2") (pinfunction "2_2") (pintype "input"))
      (node (ref "DGAR6") (pin "1") (pinfunction "1_1") (pintype "input"))
    )
    (net (code "22") (name "Net-(DGAR7-Pad2)") (class "Default")
      (node (ref "DGAR7") (pin "2") (pinfunction "2_2") (pintype "input"))
      (node (ref "DGAR8") (pin "1") (pinfunction "1_1") (pintype "input"))
    )
    (net (code "23") (name "Net-(DGAR10-Pad1)") (class "Default")
      (node (ref "DGAR10") (pin "1") (pinfunction "1_1") (pintype "input"))
      (node (ref "DGAR9") (pin "2") (pinfunction "2_2") (pintype "input"))
    )
    (net (code "24") (name "Net-(DGAR11-Pad2)") (class "Default")
      (node (ref "DGAR11") (pin "2") (pinfunction "2_2") (pintype "input"))
      (node (ref "DGAR12") (pin "1") (pinfunction "1_1") (pintype "input"))
    )
    (net (code "25") (name "Net-(DGAR13-Pad2)") (class "Default")
      (node (ref "DGAR13") (pin "2") (pinfunction "2_2") (pintype "input"))
      (node (ref "DGAR14") (pin "1") (pinfunction "1_1") (pintype "input"))
    )
    (net (code "26") (name "Net-(DGBQ1-B)") (class "Default")
      (node (ref "DGBQ1") (pin "1") (pinfunction "B_1") (pintype "unspecified"))
      (node (ref "DGBR16") (pin "2") (pinfunction "2_2") (pintype "input"))
    )
    (net (code "27") (name "Net-(DGBQ1-C-Pad2)") (class "Default")
      (node (ref "DGBQ1") (pin "2") (pinfunction "C_2") (pintype "unspecified"))
      (node (ref "DGBR3") (pin "2") (pinfunction "2_2") (pintype "input"))
    )
    (net (code "28") (name "Net-(DGBQ1-E)") (class "Default")
      (node (ref "DGBQ1") (pin "3") (pinfunction "E_3") (pintype "unspecified"))
      (node (ref "DGBQ2") (pin "4") (pinfunction "C_4") (pintype "unspecified"))
      (node (ref "DGBQ3") (pin "3") (pinfunction "E_3") (pintype "unspecified"))
      (node (ref "DGBQ4") (pin "3") (pinfunction "E_3") (pintype "unspecified"))
      (node (ref "DGBQ5") (pin "3") (pinfunction "E_3") (pintype "unspecified"))
      (node (ref "DGBQ6") (pin "3") (pinfunction "E_3") (pintype "unspecified"))
      (node (ref "DGBQ7") (pin "3") (pinfunction "E_3") (pintype "unspecified"))
      (node (ref "DGBQ8") (pin "3") (pinfunction "E_3") (pintype "unspecified"))
    )
    (net (code "29") (name "Net-(DGBQ2-B)") (class "Default")
      (node (ref "DGBQ2") (pin "1") (pinfunction "B_1") (pintype "unspecified"))
      (node (ref "DGBR15") (pin "2") (pinfunction "2_2") (pintype "input"))
    )
    (net (code "30") (name "Net-(DGBQ3-B)") (class "Default")
      (node (ref "DGBQ3") (pin "1") (pinfunction "B_1") (pintype "unspecified"))
      (node (ref "DGBR22") (pin "2") (pinfunction "2_2") (pintype "input"))
    )
    (net (code "31") (name "Net-(DGBQ3-C-Pad2)") (class "Default")
      (node (ref "DGBQ3") (pin "2") (pinfunction "C_2") (pintype "unspecified"))
      (node (ref "DGBR14") (pin "2") (pinfunction "2_2") (pintype "input"))
    )
    (net (code "32") (name "Net-(DGBQ4-B)") (class "Default")
      (node (ref "DGBQ4") (pin "1") (pinfunction "B_1") (pintype "unspecified"))
      (node (ref "DGBR17") (pin "2") (pinfunction "2_2") (pintype "input"))
    )
    (net (code "33") (name "Net-(DGBQ4-C-Pad2)") (class "Default")
      (node (ref "DGBQ4") (pin "2") (pinfunction "C_2") (pintype "unspecified"))
      (node (ref "DGBR4") (pin "2") (pinfunction "2_2") (pintype "input"))
    )
    (net (code "34") (name "Net-(DGBQ5-B)") (class "Default")
      (node (ref "DGBQ5") (pin "1") (pinfunction "B_1") (pintype "unspecified"))
      (node (ref "DGBR19") (pin "2") (pinfunction "2_2") (pintype "input"))
    )
    (net (code "35") (name "Net-(DGBQ5-C-Pad2)") (class "Default")
      (node (ref "DGBQ5") (pin "2") (pinfunction "C_2") (pintype "unspecified"))
      (node (ref "DGBR8") (pin "2") (pinfunction "2_2") (pintype "input"))
    )
    (net (code "36") (name "Net-(DGBQ6-B)") (class "Default")
      (node (ref "DGBQ6") (pin "1") (pinfunction "B_1") (pintype "unspecified"))
      (node (ref "DGBR18") (pin "2") (pinfunction "2_2") (pintype "input"))
    )
    (net (code "37") (name "Net-(DGBQ6-C-Pad2)") (class "Default")
      (node (ref "DGBQ6") (pin "2") (pinfunction "C_2") (pintype "unspecified"))
      (node (ref "DGBR6") (pin "2") (pinfunction "2_2") (pintype "input"))
    )
    (net (code "38") (name "Net-(DGBQ7-B)") (class "Default")
      (node (ref "DGBQ7") (pin "1") (pinfunction "B_1") (pintype "unspecified"))
      (node (ref "DGBR21") (pin "2") (pinfunction "2_2") (pintype "input"))
    )
    (net (code "39") (name "Net-(DGBQ7-C-Pad2)") (class "Default")
      (node (ref "DGBQ7") (pin "2") (pinfunction "C_2") (pintype "unspecified"))
      (node (ref "DGBR12") (pin "2") (pinfunction "2_2") (pintype "input"))
    )
    (net (code "40") (name "Net-(DGBQ8-B)") (class "Default")
      (node (ref "DGBQ8") (pin "1") (pinfunction "B_1") (pintype "unspecified"))
      (node (ref "DGBR20") (pin "2") (pinfunction "2_2") (pintype "input"))
    )
    (net (code "41") (name "Net-(DGBQ8-C-Pad2)") (class "Default")
      (node (ref "DGBQ8") (pin "2") (pinfunction "C_2") (pintype "unspecified"))
      (node (ref "DGBR10") (pin "2") (pinfunction "2_2") (pintype "input"))
    )
    (net (code "42") (name "Net-(DGBR1-Pad2)") (class "Default")
      (node (ref "DGBR1") (pin "2") (pinfunction "2_2") (pintype "input"))
      (node (ref "DGBR3") (pin "1") (pinfunction "1_1") (pintype "input"))
    )
    (net (code "43") (name "Net-(DGBR2-Pad2)") (class "Default")
      (node (ref "DGBR2") (pin "2") (pinfunction "2_2") (pintype "input"))
      (node (ref "DGBR4") (pin "1") (pinfunction "1_1") (pintype "input"))
    )
    (net (code "44") (name "Net-(DGBR5-Pad2)") (class "Default")
      (node (ref "DGBR5") (pin "2") (pinfunction "2_2") (pintype "input"))
      (node (ref "DGBR6") (pin "1") (pinfunction "1_1") (pintype "input"))
    )
    (net (code "45") (name "Net-(DGBR7-Pad2)") (class "Default")
      (node (ref "DGBR7") (pin "2") (pinfunction "2_2") (pintype "input"))
      (node (ref "DGBR8") (pin "1") (pinfunction "1_1") (pintype "input"))
    )
    (net (code "46") (name "Net-(DGBR10-Pad1)") (class "Default")
      (node (ref "DGBR10") (pin "1") (pinfunction "1_1") (pintype "input"))
      (node (ref "DGBR9") (pin "2") (pinfunction "2_2") (pintype "input"))
    )
    (net (code "47") (name "Net-(DGBR11-Pad2)") (class "Default")
      (node (ref "DGBR11") (pin "2") (pinfunction "2_2") (pintype "input"))
      (node (ref "DGBR12") (pin "1") (pinfunction "1_1") (pintype "input"))
    )
    (net (code "48") (name "Net-(DGBR13-Pad2)") (class "Default")
      (node (ref "DGBR13") (pin "2") (pinfunction "2_2") (pintype "input"))
      (node (ref "DGBR14") (pin "1") (pinfunction "1_1") (pintype "input"))
    )
    (net (code "49") (name "Net-(DGCQ1-B)") (class "Default")
      (node (ref "DGCQ1") (pin "1") (pinfunction "B_1") (pintype "unspecified"))
      (node (ref "DGCR16") (pin "2") (pinfunction "2_2") (pintype "input"))
    )
    (net (code "50") (name "Net-(DGCQ1-C-Pad2)") (class "Default")
      (node (ref "DGCQ1") (pin "2") (pinfunction "C_2") (pintype "unspecified"))
      (node (ref "DGCR3") (pin "2") (pinfunction "2_2") (pintype "input"))
    )
    (net (code "51") (name "Net-(DGCQ1-E)") (class "Default")
      (node (ref "DGCQ1") (pin "3") (pinfunction "E_3") (pintype "unspecified"))
      (node (ref "DGCQ2") (pin "4") (pinfunction "C_4") (pintype "unspecified"))
      (node (ref "DGCQ3") (pin "3") (pinfunction "E_3") (pintype "unspecified"))
      (node (ref "DGCQ4") (pin "3") (pinfunction "E_3") (pintype "unspecified"))
      (node (ref "DGCQ5") (pin "3") (pinfunction "E_3") (pintype "unspecified"))
      (node (ref "DGCQ6") (pin "3") (pinfunction "E_3") (pintype "unspecified"))
      (node (ref "DGCQ7") (pin "3") (pinfunction "E_3") (pintype "unspecified"))
      (node (ref "DGCQ8") (pin "3") (pinfunction "E_3") (pintype "unspecified"))
    )
    (net (code "52") (name "Net-(DGCQ2-B)") (class "Default")
      (node (ref "DGCQ2") (pin "1") (pinfunction "B_1") (pintype "unspecified"))
      (node (ref "DGCR15") (pin "2") (pinfunction "2_2") (pintype "input"))
    )
    (net (code "53") (name "Net-(DGCQ3-B)") (class "Default")
      (node (ref "DGCQ3") (pin "1") (pinfunction "B_1") (pintype "unspecified"))
      (node (ref "DGCR22") (pin "2") (pinfunction "2_2") (pintype "input"))
    )
    (net (code "54") (name "Net-(DGCQ3-C-Pad2)") (class "Default")
      (node (ref "DGCQ3") (pin "2") (pinfunction "C_2") (pintype "unspecified"))
      (node (ref "DGCR14") (pin "2") (pinfunction "2_2") (pintype "input"))
    )
    (net (code "55") (name "Net-(DGCQ4-B)") (class "Default")
      (node (ref "DGCQ4") (pin "1") (pinfunction "B_1") (pintype "unspecified"))
      (node (ref "DGCR17") (pin "2") (pinfunction "2_2") (pintype "input"))
    )
    (net (code "56") (name "Net-(DGCQ4-C-Pad2)") (class "Default")
      (node (ref "DGCQ4") (pin "2") (pinfunction "C_2") (pintype "unspecified"))
      (node (ref "DGCR4") (pin "2") (pinfunction "2_2") (pintype "input"))
    )
    (net (code "57") (name "Net-(DGCQ5-B)") (class "Default")
      (node (ref "DGCQ5") (pin "1") (pinfunction "B_1") (pintype "unspecified"))
      (node (ref "DGCR19") (pin "2") (pinfunction "2_2") (pintype "input"))
    )
    (net (code "58") (name "Net-(DGCQ5-C-Pad2)") (class "Default")
      (node (ref "DGCQ5") (pin "2") (pinfunction "C_2") (pintype "unspecified"))
      (node (ref "DGCR8") (pin "2") (pinfunction "2_2") (pintype "input"))
    )
    (net (code "59") (name "Net-(DGCQ6-B)") (class "Default")
      (node (ref "DGCQ6") (pin "1") (pinfunction "B_1") (pintype "unspecified"))
      (node (ref "DGCR18") (pin "2") (pinfunction "2_2") (pintype "input"))
    )
    (net (code "60") (name "Net-(DGCQ6-C-Pad2)") (class "Default")
      (node (ref "DGCQ6") (pin "2") (pinfunction "C_2") (pintype "unspecified"))
      (node (ref "DGCR6") (pin "2") (pinfunction "2_2") (pintype "input"))
    )
    (net (code "61") (name "Net-(DGCQ7-B)") (class "Default")
      (node (ref "DGCQ7") (pin "1") (pinfunction "B_1") (pintype "unspecified"))
      (node (ref "DGCR21") (pin "2") (pinfunction "2_2") (pintype "input"))
    )
    (net (code "62") (name "Net-(DGCQ7-C-Pad2)") (class "Default")
      (node (ref "DGCQ7") (pin "2") (pinfunction "C_2") (pintype "unspecified"))
      (node (ref "DGCR12") (pin "2") (pinfunction "2_2") (pintype "input"))
    )
    (net (code "63") (name "Net-(DGCQ8-B)") (class "Default")
      (node (ref "DGCQ8") (pin "1") (pinfunction "B_1") (pintype "unspecified"))
      (node (ref "DGCR20") (pin "2") (pinfunction "2_2") (pintype "input"))
    )
    (net (code "64") (name "Net-(DGCQ8-C-Pad2)") (class "Default")
      (node (ref "DGCQ8") (pin "2") (pinfunction "C_2") (pintype "unspecified"))
      (node (ref "DGCR10") (pin "2") (pinfunction "2_2") (pintype "input"))
    )
    (net (code "65") (name "Net-(DGCR1-Pad2)") (class "Default")
      (node (ref "DGCR1") (pin "2") (pinfunction "2_2") (pintype "input"))
      (node (ref "DGCR3") (pin "1") (pinfunction "1_1") (pintype "input"))
    )
    (net (code "66") (name "Net-(DGCR2-Pad2)") (class "Default")
      (node (ref "DGCR2") (pin "2") (pinfunction "2_2") (pintype "input"))
      (node (ref "DGCR4") (pin "1") (pinfunction "1_1") (pintype "input"))
    )
    (net (code "67") (name "Net-(DGCR5-Pad2)") (class "Default")
      (node (ref "DGCR5") (pin "2") (pinfunction "2_2") (pintype "input"))
      (node (ref "DGCR6") (pin "1") (pinfunction "1_1") (pintype "input"))
    )
    (net (code "68") (name "Net-(DGCR7-Pad2)") (class "Default")
      (node (ref "DGCR7") (pin "2") (pinfunction "2_2") (pintype "input"))
      (node (ref "DGCR8") (pin "1") (pinfunction "1_1") (pintype "input"))
    )
    (net (code "69") (name "Net-(DGCR10-Pad1)") (class "Default")
      (node (ref "DGCR10") (pin "1") (pinfunction "1_1") (pintype "input"))
      (node (ref "DGCR9") (pin "2") (pinfunction "2_2") (pintype "input"))
    )
    (net (code "70") (name "Net-(DGCR11-Pad2)") (class "Default")
      (node (ref "DGCR11") (pin "2") (pinfunction "2_2") (pintype "input"))
      (node (ref "DGCR12") (pin "1") (pinfunction "1_1") (pintype "input"))
    )
    (net (code "71") (name "Net-(DGCR13-Pad2)") (class "Default")
      (node (ref "DGCR13") (pin "2") (pinfunction "2_2") (pintype "input"))
      (node (ref "DGCR14") (pin "1") (pinfunction "1_1") (pintype "input"))
    )
    (net (code "72") (name "Net-(DGDQ1-B)") (class "Default")
      (node (ref "DGDQ1") (pin "1") (pinfunction "B_1") (pintype "unspecified"))
      (node (ref "DGDR16") (pin "2") (pinfunction "2_2") (pintype "input"))
    )
    (net (code "73") (name "Net-(DGDQ1-C-Pad2)") (class "Default")
      (node (ref "DGDQ1") (pin "2") (pinfunction "C_2") (pintype "unspecified"))
      (node (ref "DGDR3") (pin "2") (pinfunction "2_2") (pintype "input"))
    )
    (net (code "74") (name "Net-(DGDQ1-E)") (class "Default")
      (node (ref "DGDQ1") (pin "3") (pinfunction "E_3") (pintype "unspecified"))
      (node (ref "DGDQ2") (pin "4") (pinfunction "C_4") (pintype "unspecified"))
      (node (ref "DGDQ3") (pin "3") (pinfunction "E_3") (pintype "unspecified"))
      (node (ref "DGDQ4") (pin "3") (pinfunction "E_3") (pintype "unspecified"))
      (node (ref "DGDQ5") (pin "3") (pinfunction "E_3") (pintype "unspecified"))
      (node (ref "DGDQ6") (pin "3") (pinfunction "E_3") (pintype "unspecified"))
      (node (ref "DGDQ7") (pin "3") (pinfunction "E_3") (pintype "unspecified"))
      (node (ref "DGDQ8") (pin "3") (pinfunction "E_3") (pintype "unspecified"))
    )
    (net (code "75") (name "Net-(DGDQ2-B)") (class "Default")
      (node (ref "DGDQ2") (pin "1") (pinfunction "B_1") (pintype "unspecified"))
      (node (ref "DGDR15") (pin "2") (pinfunction "2_2") (pintype "input"))
    )
    (net (code "76") (name "Net-(DGDQ3-B)") (class "Default")
      (node (ref "DGDQ3") (pin "1") (pinfunction "B_1") (pintype "unspecified"))
      (node (ref "DGDR22") (pin "2") (pinfunction "2_2") (pintype "input"))
    )
    (net (code "77") (name "Net-(DGDQ3-C-Pad2)") (class "Default")
      (node (ref "DGDQ3") (pin "2") (pinfunction "C_2") (pintype "unspecified"))
      (node (ref "DGDR14") (pin "2") (pinfunction "2_2") (pintype "input"))
    )
    (net (code "78") (name "Net-(DGDQ4-B)") (class "Default")
      (node (ref "DGDQ4") (pin "1") (pinfunction "B_1") (pintype "unspecified"))
      (node (ref "DGDR17") (pin "2") (pinfunction "2_2") (pintype "input"))
    )
    (net (code "79") (name "Net-(DGDQ4-C-Pad2)") (class "Default")
      (node (ref "DGDQ4") (pin "2") (pinfunction "C_2") (pintype "unspecified"))
      (node (ref "DGDR4") (pin "2") (pinfunction "2_2") (pintype "input"))
    )
    (net (code "80") (name "Net-(DGDQ5-B)") (class "Default")
      (node (ref "DGDQ5") (pin "1") (pinfunction "B_1") (pintype "unspecified"))
      (node (ref "DGDR19") (pin "2") (pinfunction "2_2") (pintype "input"))
    )
    (net (code "81") (name "Net-(DGDQ5-C-Pad2)") (class "Default")
      (node (ref "DGDQ5") (pin "2") (pinfunction "C_2") (pintype "unspecified"))
      (node (ref "DGDR8") (pin "2") (pinfunction "2_2") (pintype "input"))
    )
    (net (code "82") (name "Net-(DGDQ6-B)") (class "Default")
      (node (ref "DGDQ6") (pin "1") (pinfunction "B_1") (pintype "unspecified"))
      (node (ref "DGDR18") (pin "2") (pinfunction "2_2") (pintype "input"))
    )
    (net (code "83") (name "Net-(DGDQ6-C-Pad2)") (class "Default")
      (node (ref "DGDQ6") (pin "2") (pinfunction "C_2") (pintype "unspecified"))
      (node (ref "DGDR6") (pin "2") (pinfunction "2_2") (pintype "input"))
    )
    (net (code "84") (name "Net-(DGDQ7-B)") (class "Default")
      (node (ref "DGDQ7") (pin "1") (pinfunction "B_1") (pintype "unspecified"))
      (node (ref "DGDR21") (pin "2") (pinfunction "2_2") (pintype "input"))
    )
    (net (code "85") (name "Net-(DGDQ7-C-Pad2)") (class "Default")
      (node (ref "DGDQ7") (pin "2") (pinfunction "C_2") (pintype "unspecified"))
      (node (ref "DGDR12") (pin "2") (pinfunction "2_2") (pintype "input"))
    )
    (net (code "86") (name "Net-(DGDQ8-B)") (class "Default")
      (node (ref "DGDQ8") (pin "1") (pinfunction "B_1") (pintype "unspecified"))
      (node (ref "DGDR20") (pin "2") (pinfunction "2_2") (pintype "input"))
    )
    (net (code "87") (name "Net-(DGDQ8-C-Pad2)") (class "Default")
      (node (ref "DGDQ8") (pin "2") (pinfunction "C_2") (pintype "unspecified"))
      (node (ref "DGDR10") (pin "2") (pinfunction "2_2") (pintype "input"))
    )
    (net (code "88") (name "Net-(DGDR1-Pad2)") (class "Default")
      (node (ref "DGDR1") (pin "2") (pinfunction "2_2") (pintype "input"))
      (node (ref "DGDR3") (pin "1") (pinfunction "1_1") (pintype "input"))
    )
    (net (code "89") (name "Net-(DGDR2-Pad2)") (class "Default")
      (node (ref "DGDR2") (pin "2") (pinfunction "2_2") (pintype "input"))
      (node (ref "DGDR4") (pin "1") (pinfunction "1_1") (pintype "input"))
    )
    (net (code "90") (name "Net-(DGDR5-Pad2)") (class "Default")
      (node (ref "DGDR5") (pin "2") (pinfunction "2_2") (pintype "input"))
      (node (ref "DGDR6") (pin "1") (pinfunction "1_1") (pintype "input"))
    )
    (net (code "91") (name "Net-(DGDR7-Pad2)") (class "Default")
      (node (ref "DGDR7") (pin "2") (pinfunction "2_2") (pintype "input"))
      (node (ref "DGDR8") (pin "1") (pinfunction "1_1") (pintype "input"))
    )
    (net (code "92") (name "Net-(DGDR10-Pad1)") (class "Default")
      (node (ref "DGDR10") (pin "1") (pinfunction "1_1") (pintype "input"))
      (node (ref "DGDR9") (pin "2") (pinfunction "2_2") (pintype "input"))
    )
    (net (code "93") (name "Net-(DGDR11-Pad2)") (class "Default")
      (node (ref "DGDR11") (pin "2") (pinfunction "2_2") (pintype "input"))
      (node (ref "DGDR12") (pin "1") (pinfunction "1_1") (pintype "input"))
    )
    (net (code "94") (name "Net-(DGDR13-Pad2)") (class "Default")
      (node (ref "DGDR13") (pin "2") (pinfunction "2_2") (pintype "input"))
      (node (ref "DGDR14") (pin "1") (pinfunction "1_1") (pintype "input"))
    )
    (net (code "95") (name "unconnected-(C1-Pad1)") (class "Default")
      (node (ref "C1") (pin "1") (pinfunction "1_1") (pintype "input"))
    )
    (net (code "96") (name "unconnected-(C1-Pad2)") (class "Default")
      (node (ref "C1") (pin "2") (pinfunction "2_2") (pintype "input"))
    )
    (net (code "97") (name "unconnected-(C2-Pad1)") (class "Default")
      (node (ref "C2") (pin "1") (pinfunction "1_1") (pintype "unspecified"))
    )
    (net (code "98") (name "unconnected-(C2-Pad2)") (class "Default")
      (node (ref "C2") (pin "2") (pinfunction "2_2") (pintype "unspecified"))
    )
    (net (code "99") (name "unconnected-(C3-Pad1)") (class "Default")
      (node (ref "C3") (pin "1") (pinfunction "1_1") (pintype "input"))
    )
    (net (code "100") (name "unconnected-(C3-Pad2)") (class "Default")
      (node (ref "C3") (pin "2") (pinfunction "2_2") (pintype "input"))
    )
    (net (code "101") (name "unconnected-(C4-Pad1)") (class "Default")
      (node (ref "C4") (pin "1") (pinfunction "1_1") (pintype "input"))
    )
    (net (code "102") (name "unconnected-(C4-Pad2)") (class "Default")
      (node (ref "C4") (pin "2") (pinfunction "2_2") (pintype "input"))
    )
    (net (code "103") (name "unconnected-(C5-Pad1)") (class "Default")
      (node (ref "C5") (pin "1") (pinfunction "1_1") (pintype "input"))
    )
    (net (code "104") (name "unconnected-(C5-Pad2)") (class "Default")
      (node (ref "C5") (pin "2") (pinfunction "2_2") (pintype "input"))
    )
    (net (code "105") (name "unconnected-(C6-Pad1)") (class "Default")
      (node (ref "C6") (pin "1") (pinfunction "1_1") (pintype "input"))
    )
    (net (code "106") (name "unconnected-(C6-Pad2)") (class "Default")
      (node (ref "C6") (pin "2") (pinfunction "2_2") (pintype "input"))
    )
    (net (code "107") (name "unconnected-(DGAQ1-C-Pad4)") (class "Default")
      (node (ref "DGAQ1") (pin "4") (pinfunction "C_4") (pintype "unspecified"))
    )
    (net (code "108") (name "unconnected-(DGAQ2-C-Pad2)") (class "Default")
      (node (ref "DGAQ2") (pin "2") (pinfunction "C_2") (pintype "unspecified"))
    )
    (net (code "109") (name "unconnected-(DGAQ3-C-Pad4)") (class "Default")
      (node (ref "DGAQ3") (pin "4") (pinfunction "C_4") (pintype "unspecified"))
    )
    (net (code "110") (name "unconnected-(DGAQ4-C-Pad4)") (class "Default")
      (node (ref "DGAQ4") (pin "4") (pinfunction "C_4") (pintype "unspecified"))
    )
    (net (code "111") (name "unconnected-(DGAQ5-C-Pad4)") (class "Default")
      (node (ref "DGAQ5") (pin "4") (pinfunction "C_4") (pintype "unspecified"))
    )
    (net (code "112") (name "unconnected-(DGAQ6-C-Pad4)") (class "Default")
      (node (ref "DGAQ6") (pin "4") (pinfunction "C_4") (pintype "unspecified"))
    )
    (net (code "113") (name "unconnected-(DGAQ7-C-Pad4)") (class "Default")
      (node (ref "DGAQ7") (pin "4") (pinfunction "C_4") (pintype "unspecified"))
    )
    (net (code "114") (name "unconnected-(DGAQ8-C-Pad4)") (class "Default")
      (node (ref "DGAQ8") (pin "4") (pinfunction "C_4") (pintype "unspecified"))
    )
    (net (code "115") (name "unconnected-(DGAR1-Pad1)") (class "Default")
      (node (ref "DGAR1") (pin "1") (pinfunction "1_1") (pintype "input"))
    )
    (net (code "116") (name "unconnected-(DGAR2-Pad1)") (class "Default")
      (node (ref "DGAR2") (pin "1") (pinfunction "1_1") (pintype "input"))
    )
    (net (code "117") (name "unconnected-(DGAR5-Pad1)") (class "Default")
      (node (ref "DGAR5") (pin "1") (pinfunction "1_1") (pintype "input"))
    )
    (net (code "118") (name "unconnected-(DGAR7-Pad1)") (class "Default")
      (node (ref "DGAR7") (pin "1") (pinfunction "1_1") (pintype "input"))
    )
    (net (code "119") (name "unconnected-(DGAR9-Pad1)") (class "Default")
      (node (ref "DGAR9") (pin "1") (pinfunction "1_1") (pintype "input"))
    )
    (net (code "120") (name "unconnected-(DGAR11-Pad1)") (class "Default")
      (node (ref "DGAR11") (pin "1") (pinfunction "1_1") (pintype "input"))
    )
    (net (code "121") (name "unconnected-(DGAR13-Pad1)") (class "Default")
      (node (ref "DGAR13") (pin "1") (pinfunction "1_1") (pintype "input"))
    )
    (net (code "122") (name "unconnected-(DGAR15-Pad1)") (class "Default")
      (node (ref "DGAR15") (pin "1") (pinfunction "1_1") (pintype "input"))
    )
    (net (code "123") (name "unconnected-(DGAR16-Pad1)") (class "Default")
      (node (ref "DGAR16") (pin "1") (pinfunction "1_1") (pintype "input"))
    )
    (net (code "124") (name "unconnected-(DGAR17-Pad1)") (class "Default")
      (node (ref "DGAR17") (pin "1") (pinfunction "1_1") (pintype "input"))
    )
    (net (code "125") (name "unconnected-(DGAR18-Pad1)") (class "Default")
      (node (ref "DGAR18") (pin "1") (pinfunction "1_1") (pintype "input"))
    )
    (net (code "126") (name "unconnected-(DGAR19-Pad1)") (class "Default")
      (node (ref "DGAR19") (pin "1") (pinfunction "1_1") (pintype "input"))
    )
    (net (code "127") (name "unconnected-(DGAR20-Pad1)") (class "Default")
      (node (ref "DGAR20") (pin "1") (pinfunction "1_1") (pintype "input"))
    )
    (net (code "128") (name "unconnected-(DGAR21-Pad1)") (class "Default")
      (node (ref "DGAR21") (pin "1") (pinfunction "1_1") (pintype "input"))
    )
    (net (code "129") (name "unconnected-(DGAR22-Pad1)") (class "Default")
      (node (ref "DGAR22") (pin "1") (pinfunction "1_1") (pintype "input"))
    )
    (net (code "130") (name "unconnected-(DGBQ1-C-Pad4)") (class "Default")
      (node (ref "DGBQ1") (pin "4") (pinfunction "C_4") (pintype "unspecified"))
    )
    (net (code "131") (name "unconnected-(DGBQ2-C-Pad2)") (class "Default")
      (node (ref "DGBQ2") (pin "2") (pinfunction "C_2") (pintype "unspecified"))
    )
    (net (code "132") (name "unconnected-(DGBQ3-C-Pad4)") (class "Default")
      (node (ref "DGBQ3") (pin "4") (pinfunction "C_4") (pintype "unspecified"))
    )
    (net (code "133") (name "unconnected-(DGBQ4-C-Pad4)") (class "Default")
      (node (ref "DGBQ4") (pin "4") (pinfunction "C_4") (pintype "unspecified"))
    )
    (net (code "134") (name "unconnected-(DGBQ5-C-Pad4)") (class "Default")
      (node (ref "DGBQ5") (pin "4") (pinfunction "C_4") (pintype "unspecified"))
    )
    (net (code "135") (name "unconnected-(DGBQ6-C-Pad4)") (class "Default")
      (node (ref "DGBQ6") (pin "4") (pinfunction "C_4") (pintype "unspecified"))
    )
    (net (code "136") (name "unconnected-(DGBQ7-C-Pad4)") (class "Default")
      (node (ref "DGBQ7") (pin "4") (pinfunction "C_4") (pintype "unspecified"))
    )
    (net (code "137") (name "unconnected-(DGBQ8-C-Pad4)") (class "Default")
      (node (ref "DGBQ8") (pin "4") (pinfunction "C_4") (pintype "unspecified"))
    )
    (net (code "138") (name "unconnected-(DGBR1-Pad1)") (class "Default")
      (node (ref "DGBR1") (pin "1") (pinfunction "1_1") (pintype "input"))
    )
    (net (code "139") (name "unconnected-(DGBR2-Pad1)") (class "Default")
      (node (ref "DGBR2") (pin "1") (pinfunction "1_1") (pintype "input"))
    )
    (net (code "140") (name "unconnected-(DGBR5-Pad1)") (class "Default")
      (node (ref "DGBR5") (pin "1") (pinfunction "1_1") (pintype "input"))
    )
    (net (code "141") (name "unconnected-(DGBR7-Pad1)") (class "Default")
      (node (ref "DGBR7") (pin "1") (pinfunction "1_1") (pintype "input"))
    )
    (net (code "142") (name "unconnected-(DGBR9-Pad1)") (class "Default")
      (node (ref "DGBR9") (pin "1") (pinfunction "1_1") (pintype "input"))
    )
    (net (code "143") (name "unconnected-(DGBR11-Pad1)") (class "Default")
      (node (ref "DGBR11") (pin "1") (pinfunction "1_1") (pintype "input"))
    )
    (net (code "144") (name "unconnected-(DGBR13-Pad1)") (class "Default")
      (node (ref "DGBR13") (pin "1") (pinfunction "1_1") (pintype "input"))
    )
    (net (code "145") (name "unconnected-(DGBR15-Pad1)") (class "Default")
      (node (ref "DGBR15") (pin "1") (pinfunction "1_1") (pintype "input"))
    )
    (net (code "146") (name "unconnected-(DGBR16-Pad1)") (class "Default")
      (node (ref "DGBR16") (pin "1") (pinfunction "1_1") (pintype "input"))
    )
    (net (code "147") (name "unconnected-(DGBR17-Pad1)") (class "Default")
      (node (ref "DGBR17") (pin "1") (pinfunction "1_1") (pintype "input"))
    )
    (net (code "148") (name "unconnected-(DGBR18-Pad1)") (class "Default")
      (node (ref "DGBR18") (pin "1") (pinfunction "1_1") (pintype "input"))
    )
    (net (code "149") (name "unconnected-(DGBR19-Pad1)") (class "Default")
      (node (ref "DGBR19") (pin "1") (pinfunction "1_1") (pintype "input"))
    )
    (net (code "150") (name "unconnected-(DGBR20-Pad1)") (class "Default")
      (node (ref "DGBR20") (pin "1") (pinfunction "1_1") (pintype "input"))
    )
    (net (code "151") (name "unconnected-(DGBR21-Pad1)") (class "Default")
      (node (ref "DGBR21") (pin "1") (pinfunction "1_1") (pintype "input"))
    )
    (net (code "152") (name "unconnected-(DGBR22-Pad1)") (class "Default")
      (node (ref "DGBR22") (pin "1") (pinfunction "1_1") (pintype "input"))
    )
    (net (code "153") (name "unconnected-(DGCQ1-C-Pad4)") (class "Default")
      (node (ref "DGCQ1") (pin "4") (pinfunction "C_4") (pintype "unspecified"))
    )
    (net (code "154") (name "unconnected-(DGCQ2-C-Pad2)") (class "Default")
      (node (ref "DGCQ2") (pin "2") (pinfunction "C_2") (pintype "unspecified"))
    )
    (net (code "155") (name "unconnected-(DGCQ3-C-Pad4)") (class "Default")
      (node (ref "DGCQ3") (pin "4") (pinfunction "C_4") (pintype "unspecified"))
    )
    (net (code "156") (name "unconnected-(DGCQ4-C-Pad4)") (class "Default")
      (node (ref "DGCQ4") (pin "4") (pinfunction "C_4") (pintype "unspecified"))
    )
    (net (code "157") (name "unconnected-(DGCQ5-C-Pad4)") (class "Default")
      (node (ref "DGCQ5") (pin "4") (pinfunction "C_4") (pintype "unspecified"))
    )
    (net (code "158") (name "unconnected-(DGCQ6-C-Pad4)") (class "Default")
      (node (ref "DGCQ6") (pin "4") (pinfunction "C_4") (pintype "unspecified"))
    )
    (net (code "159") (name "unconnected-(DGCQ7-C-Pad4)") (class "Default")
      (node (ref "DGCQ7") (pin "4") (pinfunction "C_4") (pintype "unspecified"))
    )
    (net (code "160") (name "unconnected-(DGCQ8-C-Pad4)") (class "Default")
      (node (ref "DGCQ8") (pin "4") (pinfunction "C_4") (pintype "unspecified"))
    )
    (net (code "161") (name "unconnected-(DGCR1-Pad1)") (class "Default")
      (node (ref "DGCR1") (pin "1") (pinfunction "1_1") (pintype "input"))
    )
    (net (code "162") (name "unconnected-(DGCR2-Pad1)") (class "Default")
      (node (ref "DGCR2") (pin "1") (pinfunction "1_1") (pintype "input"))
    )
    (net (code "163") (name "unconnected-(DGCR5-Pad1)") (class "Default")
      (node (ref "DGCR5") (pin "1") (pinfunction "1_1") (pintype "input"))
    )
    (net (code "164") (name "unconnected-(DGCR7-Pad1)") (class "Default")
      (node (ref "DGCR7") (pin "1") (pinfunction "1_1") (pintype "input"))
    )
    (net (code "165") (name "unconnected-(DGCR9-Pad1)") (class "Default")
      (node (ref "DGCR9") (pin "1") (pinfunction "1_1") (pintype "input"))
    )
    (net (code "166") (name "unconnected-(DGCR11-Pad1)") (class "Default")
      (node (ref "DGCR11") (pin "1") (pinfunction "1_1") (pintype "input"))
    )
    (net (code "167") (name "unconnected-(DGCR13-Pad1)") (class "Default")
      (node (ref "DGCR13") (pin "1") (pinfunction "1_1") (pintype "input"))
    )
    (net (code "168") (name "unconnected-(DGCR15-Pad1)") (class "Default")
      (node (ref "DGCR15") (pin "1") (pinfunction "1_1") (pintype "input"))
    )
    (net (code "169") (name "unconnected-(DGCR16-Pad1)") (class "Default")
      (node (ref "DGCR16") (pin "1") (pinfunction "1_1") (pintype "input"))
    )
    (net (code "170") (name "unconnected-(DGCR17-Pad1)") (class "Default")
      (node (ref "DGCR17") (pin "1") (pinfunction "1_1") (pintype "input"))
    )
    (net (code "171") (name "unconnected-(DGCR18-Pad1)") (class "Default")
      (node (ref "DGCR18") (pin "1") (pinfunction "1_1") (pintype "input"))
    )
    (net (code "172") (name "unconnected-(DGCR19-Pad1)") (class "Default")
      (node (ref "DGCR19") (pin "1") (pinfunction "1_1") (pintype "input"))
    )
    (net (code "173") (name "unconnected-(DGCR20-Pad1)") (class "Default")
      (node (ref "DGCR20") (pin "1") (pinfunction "1_1") (pintype "input"))
    )
    (net (code "174") (name "unconnected-(DGCR21-Pad1)") (class "Default")
      (node (ref "DGCR21") (pin "1") (pinfunction "1_1") (pintype "input"))
    )
    (net (code "175") (name "unconnected-(DGCR22-Pad1)") (class "Default")
      (node (ref "DGCR22") (pin "1") (pinfunction "1_1") (pintype "input"))
    )
    (net (code "176") (name "unconnected-(DGDQ1-C-Pad4)") (class "Default")
      (node (ref "DGDQ1") (pin "4") (pinfunction "C_4") (pintype "unspecified"))
    )
    (net (code "177") (name "unconnected-(DGDQ2-C-Pad2)") (class "Default")
      (node (ref "DGDQ2") (pin "2") (pinfunction "C_2") (pintype "unspecified"))
    )
    (net (code "178") (name "unconnected-(DGDQ3-C-Pad4)") (class "Default")
      (node (ref "DGDQ3") (pin "4") (pinfunction "C_4") (pintype "unspecified"))
    )
    (net (code "179") (name "unconnected-(DGDQ4-C-Pad4)") (class "Default")
      (node (ref "DGDQ4") (pin "4") (pinfunction "C_4") (pintype "unspecified"))
    )
    (net (code "180") (name "unconnected-(DGDQ5-C-Pad4)") (class "Default")
      (node (ref "DGDQ5") (pin "4") (pinfunction "C_4") (pintype "unspecified"))
    )
    (net (code "181") (name "unconnected-(DGDQ6-C-Pad4)") (class "Default")
      (node (ref "DGDQ6") (pin "4") (pinfunction "C_4") (pintype "unspecified"))
    )
    (net (code "182") (name "unconnected-(DGDQ7-C-Pad4)") (class "Default")
      (node (ref "DGDQ7") (pin "4") (pinfunction "C_4") (pintype "unspecified"))
    )
    (net (code "183") (name "unconnected-(DGDQ8-C-Pad4)") (class "Default")
      (node (ref "DGDQ8") (pin "4") (pinfunction "C_4") (pintype "unspecified"))
    )
    (net (code "184") (name "unconnected-(DGDR1-Pad1)") (class "Default")
      (node (ref "DGDR1") (pin "1") (pinfunction "1_1") (pintype "input"))
    )
    (net (code "185") (name "unconnected-(DGDR2-Pad1)") (class "Default")
      (node (ref "DGDR2") (pin "1") (pinfunction "1_1") (pintype "input"))
    )
    (net (code "186") (name "unconnected-(DGDR5-Pad1)") (class "Default")
      (node (ref "DGDR5") (pin "1") (pinfunction "1_1") (pintype "input"))
    )
    (net (code "187") (name "unconnected-(DGDR7-Pad1)") (class "Default")
      (node (ref "DGDR7") (pin "1") (pinfunction "1_1") (pintype "input"))
    )
    (net (code "188") (name "unconnected-(DGDR9-Pad1)") (class "Default")
      (node (ref "DGDR9") (pin "1") (pinfunction "1_1") (pintype "input"))
    )
    (net (code "189") (name "unconnected-(DGDR11-Pad1)") (class "Default")
      (node (ref "DGDR11") (pin "1") (pinfunction "1_1") (pintype "input"))
    )
    (net (code "190") (name "unconnected-(DGDR13-Pad1)") (class "Default")
      (node (ref "DGDR13") (pin "1") (pinfunction "1_1") (pintype "input"))
    )
    (net (code "191") (name "unconnected-(DGDR15-Pad1)") (class "Default")
      (node (ref "DGDR15") (pin "1") (pinfunction "1_1") (pintype "input"))
    )
    (net (code "192") (name "unconnected-(DGDR16-Pad1)") (class "Default")
      (node (ref "DGDR16") (pin "1") (pinfunction "1_1") (pintype "input"))
    )
    (net (code "193") (name "unconnected-(DGDR17-Pad1)") (class "Default")
      (node (ref "DGDR17") (pin "1") (pinfunction "1_1") (pintype "input"))
    )
    (net (code "194") (name "unconnected-(DGDR18-Pad1)") (class "Default")
      (node (ref "DGDR18") (pin "1") (pinfunction "1_1") (pintype "input"))
    )
    (net (code "195") (name "unconnected-(DGDR19-Pad1)") (class "Default")
      (node (ref "DGDR19") (pin "1") (pinfunction "1_1") (pintype "input"))
    )
    (net (code "196") (name "unconnected-(DGDR20-Pad1)") (class "Default")
      (node (ref "DGDR20") (pin "1") (pinfunction "1_1") (pintype "input"))
    )
    (net (code "197") (name "unconnected-(DGDR21-Pad1)") (class "Default")
      (node (ref "DGDR21") (pin "1") (pinfunction "1_1") (pintype "input"))
    )
    (net (code "198") (name "unconnected-(DGDR22-Pad1)") (class "Default")
      (node (ref "DGDR22") (pin "1") (pinfunction "1_1") (pintype "input"))
    )
    (net (code "199") (name "unconnected-(H1-Pad1)") (class "Default")
      (node (ref "H1") (pin "1") (pinfunction "1_1") (pintype "unspecified"))
    )
    (net (code "200") (name "unconnected-(H1-Pad2)") (class "Default")
      (node (ref "H1") (pin "2") (pinfunction "2_2") (pintype "unspecified"))
    )
    (net (code "201") (name "unconnected-(H1-Pad3)") (class "Default")
      (node (ref "H1") (pin "3") (pinfunction "3_3") (pintype "unspecified"))
    )
    (net (code "202") (name "unconnected-(H1-Pad4)") (class "Default")
      (node (ref "H1") (pin "4") (pinfunction "4_4") (pintype "unspecified"))
    )
    (net (code "203") (name "unconnected-(H1-Pad5)") (class "Default")
      (node (ref "H1") (pin "5") (pinfunction "5_5") (pintype "unspecified"))
    )
    (net (code "204") (name "unconnected-(H1-Pad6)") (class "Default")
      (node (ref "H1") (pin "6") (pinfunction "6_6") (pintype "unspecified"))
    )
    (net (code "205") (name "unconnected-(H1-Pad7)") (class "Default")
      (node (ref "H1") (pin "7") (pinfunction "7_7") (pintype "unspecified"))
    )
    (net (code "206") (name "unconnected-(H1-Pad8)") (class "Default")
      (node (ref "H1") (pin "8") (pinfunction "8_8") (pintype "unspecified"))
    )
    (net (code "207") (name "unconnected-(H1-Pad9)") (class "Default")
      (node (ref "H1") (pin "9") (pinfunction "9_9") (pintype "unspecified"))
    )
    (net (code "208") (name "unconnected-(H1-Pad10)") (class "Default")
      (node (ref "H1") (pin "10") (pinfunction "10_10") (pintype "unspecified"))
    )
    (net (code "209") (name "unconnected-(H1-Pad11)") (class "Default")
      (node (ref "H1") (pin "11") (pinfunction "11_11") (pintype "unspecified"))
    )
    (net (code "210") (name "unconnected-(H1-Pad12)") (class "Default")
      (node (ref "H1") (pin "12") (pinfunction "12_12") (pintype "unspecified"))
    )
    (net (code "211") (name "unconnected-(H1-Pad13)") (class "Default")
      (node (ref "H1") (pin "13") (pinfunction "13_13") (pintype "unspecified"))
    )
    (net (code "212") (name "unconnected-(H1-Pad14)") (class "Default")
      (node (ref "H1") (pin "14") (pinfunction "14_14") (pintype "unspecified"))
    )
    (net (code "213") (name "unconnected-(H1-Pad15)") (class "Default")
      (node (ref "H1") (pin "15") (pinfunction "15_15") (pintype "unspecified"))
    )
    (net (code "214") (name "unconnected-(H2-Pad1)") (class "Default")
      (node (ref "H2") (pin "1") (pinfunction "1_1") (pintype "unspecified"))
    )
    (net (code "215") (name "unconnected-(H2-Pad2)") (class "Default")
      (node (ref "H2") (pin "2") (pinfunction "2_2") (pintype "unspecified"))
    )
    (net (code "216") (name "unconnected-(H2-Pad3)") (class "Default")
      (node (ref "H2") (pin "3") (pinfunction "3_3") (pintype "unspecified"))
    )
    (net (code "217") (name "unconnected-(H2-Pad4)") (class "Default")
      (node (ref "H2") (pin "4") (pinfunction "4_4") (pintype "unspecified"))
    )
    (net (code "218") (name "unconnected-(H2-Pad5)") (class "Default")
      (node (ref "H2") (pin "5") (pinfunction "5_5") (pintype "unspecified"))
    )
    (net (code "219") (name "unconnected-(H2-Pad6)") (class "Default")
      (node (ref "H2") (pin "6") (pinfunction "6_6") (pintype "unspecified"))
    )
    (net (code "220") (name "unconnected-(H2-Pad7)") (class "Default")
      (node (ref "H2") (pin "7") (pinfunction "7_7") (pintype "unspecified"))
    )
    (net (code "221") (name "unconnected-(H2-Pad8)") (class "Default")
      (node (ref "H2") (pin "8") (pinfunction "8_8") (pintype "unspecified"))
    )
    (net (code "222") (name "unconnected-(H2-Pad9)") (class "Default")
      (node (ref "H2") (pin "9") (pinfunction "9_9") (pintype "unspecified"))
    )
    (net (code "223") (name "unconnected-(H2-Pad10)") (class "Default")
      (node (ref "H2") (pin "10") (pinfunction "10_10") (pintype "unspecified"))
    )
    (net (code "224") (name "unconnected-(H2-Pad11)") (class "Default")
      (node (ref "H2") (pin "11") (pinfunction "11_11") (pintype "unspecified"))
    )
    (net (code "225") (name "unconnected-(H2-Pad12)") (class "Default")
      (node (ref "H2") (pin "12") (pinfunction "12_12") (pintype "unspecified"))
    )
    (net (code "226") (name "unconnected-(H2-Pad13)") (class "Default")
      (node (ref "H2") (pin "13") (pinfunction "13_13") (pintype "unspecified"))
    )
    (net (code "227") (name "unconnected-(H2-Pad14)") (class "Default")
      (node (ref "H2") (pin "14") (pinfunction "14_14") (pintype "unspecified"))
    )
    (net (code "228") (name "unconnected-(H2-Pad15)") (class "Default")
      (node (ref "H2") (pin "15") (pinfunction "15_15") (pintype "unspecified"))
    )
    (net (code "229") (name "unconnected-(SW1-Pad1)") (class "Default")
      (node (ref "SW1") (pin "1") (pinfunction "1_1") (pintype "unspecified"))
    )
    (net (code "230") (name "unconnected-(SW1-Pad2)") (class "Default")
      (node (ref "SW1") (pin "2") (pinfunction "2_2") (pintype "unspecified"))
    )
    (net (code "231") (name "unconnected-(SW1-Pad3)") (class "Default")
      (node (ref "SW1") (pin "3") (pinfunction "3_3") (pintype "unspecified"))
    )
    (net (code "232") (name "unconnected-(SW1-Pad4)") (class "Default")
      (node (ref "SW1") (pin "4") (pinfunction "4_4") (pintype "unspecified"))
    )
    (net (code "233") (name "unconnected-(SW2-Pad1)") (class "Default")
      (node (ref "SW2") (pin "1") (pinfunction "1_1") (pintype "unspecified"))
    )
    (net (code "234") (name "unconnected-(SW2-Pad2)") (class "Default")
      (node (ref "SW2") (pin "2") (pinfunction "2_2") (pintype "unspecified"))
    )
    (net (code "235") (name "unconnected-(SW2-Pad3)") (class "Default")
      (node (ref "SW2") (pin "3") (pinfunction "3_3") (pintype "unspecified"))
    )
    (net (code "236") (name "unconnected-(SW2-Pad4)") (class "Default")
      (node (ref "SW2") (pin "4") (pinfunction "4_4") (pintype "unspecified"))
    )
    (net (code "237") (name "unconnected-(SW3-Pad1)") (class "Default")
      (node (ref "SW3") (pin "1") (pinfunction "1_1") (pintype "unspecified"))
    )
    (net (code "238") (name "unconnected-(SW3-Pad2)") (class "Default")
      (node (ref "SW3") (pin "2") (pinfunction "2_2") (pintype "unspecified"))
    )
    (net (code "239") (name "unconnected-(SW3-Pad3)") (class "Default")
      (node (ref "SW3") (pin "3") (pinfunction "3_3") (pintype "unspecified"))
    )
    (net (code "240") (name "unconnected-(SW3-Pad4)") (class "Default")
      (node (ref "SW3") (pin "4") (pinfunction "4_4") (pintype "unspecified"))
    )
    (net (code "241") (name "unconnected-(SW4-Pad1)") (class "Default")
      (node (ref "SW4") (pin "1") (pinfunction "1_1") (pintype "unspecified"))
    )
    (net (code "242") (name "unconnected-(SW4-Pad2)") (class "Default")
      (node (ref "SW4") (pin "2") (pinfunction "2_2") (pintype "unspecified"))
    )
    (net (code "243") (name "unconnected-(SW4-Pad3)") (class "Default")
      (node (ref "SW4") (pin "3") (pinfunction "3_3") (pintype "unspecified"))
    )
    (net (code "244") (name "unconnected-(SW4-Pad4)") (class "Default")
      (node (ref "SW4") (pin "4") (pinfunction "4_4") (pintype "unspecified"))
    )
    (net (code "245") (name "unconnected-(U1-CLK-Pad3)") (class "Default")
      (node (ref "U1") (pin "3") (pinfunction "CLK_3") (pintype "unspecified"))
    )
    (net (code "246") (name "unconnected-(U1-DATA-Pad2)") (class "Default")
      (node (ref "U1") (pin "2") (pinfunction "DATA_2") (pintype "unspecified"))
    )
    (net (code "247") (name "unconnected-(U1-OUT{slash}EN-Pad15)") (class "Default")
      (node (ref "U1") (pin "15") (pinfunction "OUT/EN_15") (pintype "unspecified"))
    )
    (net (code "248") (name "unconnected-(U1-Q1-Pad4)") (class "Default")
      (node (ref "U1") (pin "4") (pinfunction "Q1_4") (pintype "unspecified"))
    )
    (net (code "249") (name "unconnected-(U1-Q2-Pad5)") (class "Default")
      (node (ref "U1") (pin "5") (pinfunction "Q2_5") (pintype "unspecified"))
    )
    (net (code "250") (name "unconnected-(U1-Q3-Pad6)") (class "Default")
      (node (ref "U1") (pin "6") (pinfunction "Q3_6") (pintype "unspecified"))
    )
    (net (code "251") (name "unconnected-(U1-Q4-Pad7)") (class "Default")
      (node (ref "U1") (pin "7") (pinfunction "Q4_7") (pintype "unspecified"))
    )
    (net (code "252") (name "unconnected-(U1-Q5-Pad14)") (class "Default")
      (node (ref "U1") (pin "14") (pinfunction "Q5_14") (pintype "unspecified"))
    )
    (net (code "253") (name "unconnected-(U1-Q6-Pad13)") (class "Default")
      (node (ref "U1") (pin "13") (pinfunction "Q6_13") (pintype "unspecified"))
    )
    (net (code "254") (name "unconnected-(U1-Q7-Pad12)") (class "Default")
      (node (ref "U1") (pin "12") (pinfunction "Q7_12") (pintype "unspecified"))
    )
    (net (code "255") (name "unconnected-(U1-Q8-Pad11)") (class "Default")
      (node (ref "U1") (pin "11") (pinfunction "Q8_11") (pintype "unspecified"))
    )
    (net (code "256") (name "unconnected-(U1-QS-Pad9)") (class "Default")
      (node (ref "U1") (pin "9") (pinfunction "QS_9") (pintype "unspecified"))
    )
    (net (code "257") (name "unconnected-(U1-QS{slash}2-Pad10)") (class "Default")
      (node (ref "U1") (pin "10") (pinfunction "QS/2_10") (pintype "unspecified"))
    )
    (net (code "258") (name "unconnected-(U1-STROBE-Pad1)") (class "Default")
      (node (ref "U1") (pin "1") (pinfunction "STROBE_1") (pintype "unspecified"))
    )
    (net (code "259") (name "unconnected-(U1-VDD-Pad16)") (class "Default")
      (node (ref "U1") (pin "16") (pinfunction "VDD_16") (pintype "unspecified"))
    )
    (net (code "260") (name "unconnected-(U1-VSS-Pad8)") (class "Default")
      (node (ref "U1") (pin "8") (pinfunction "VSS_8") (pintype "unspecified"))
    )
  )
)
